# Modulator_V1p2.net
KiCad netlist of a schematic drawn in EAGLE
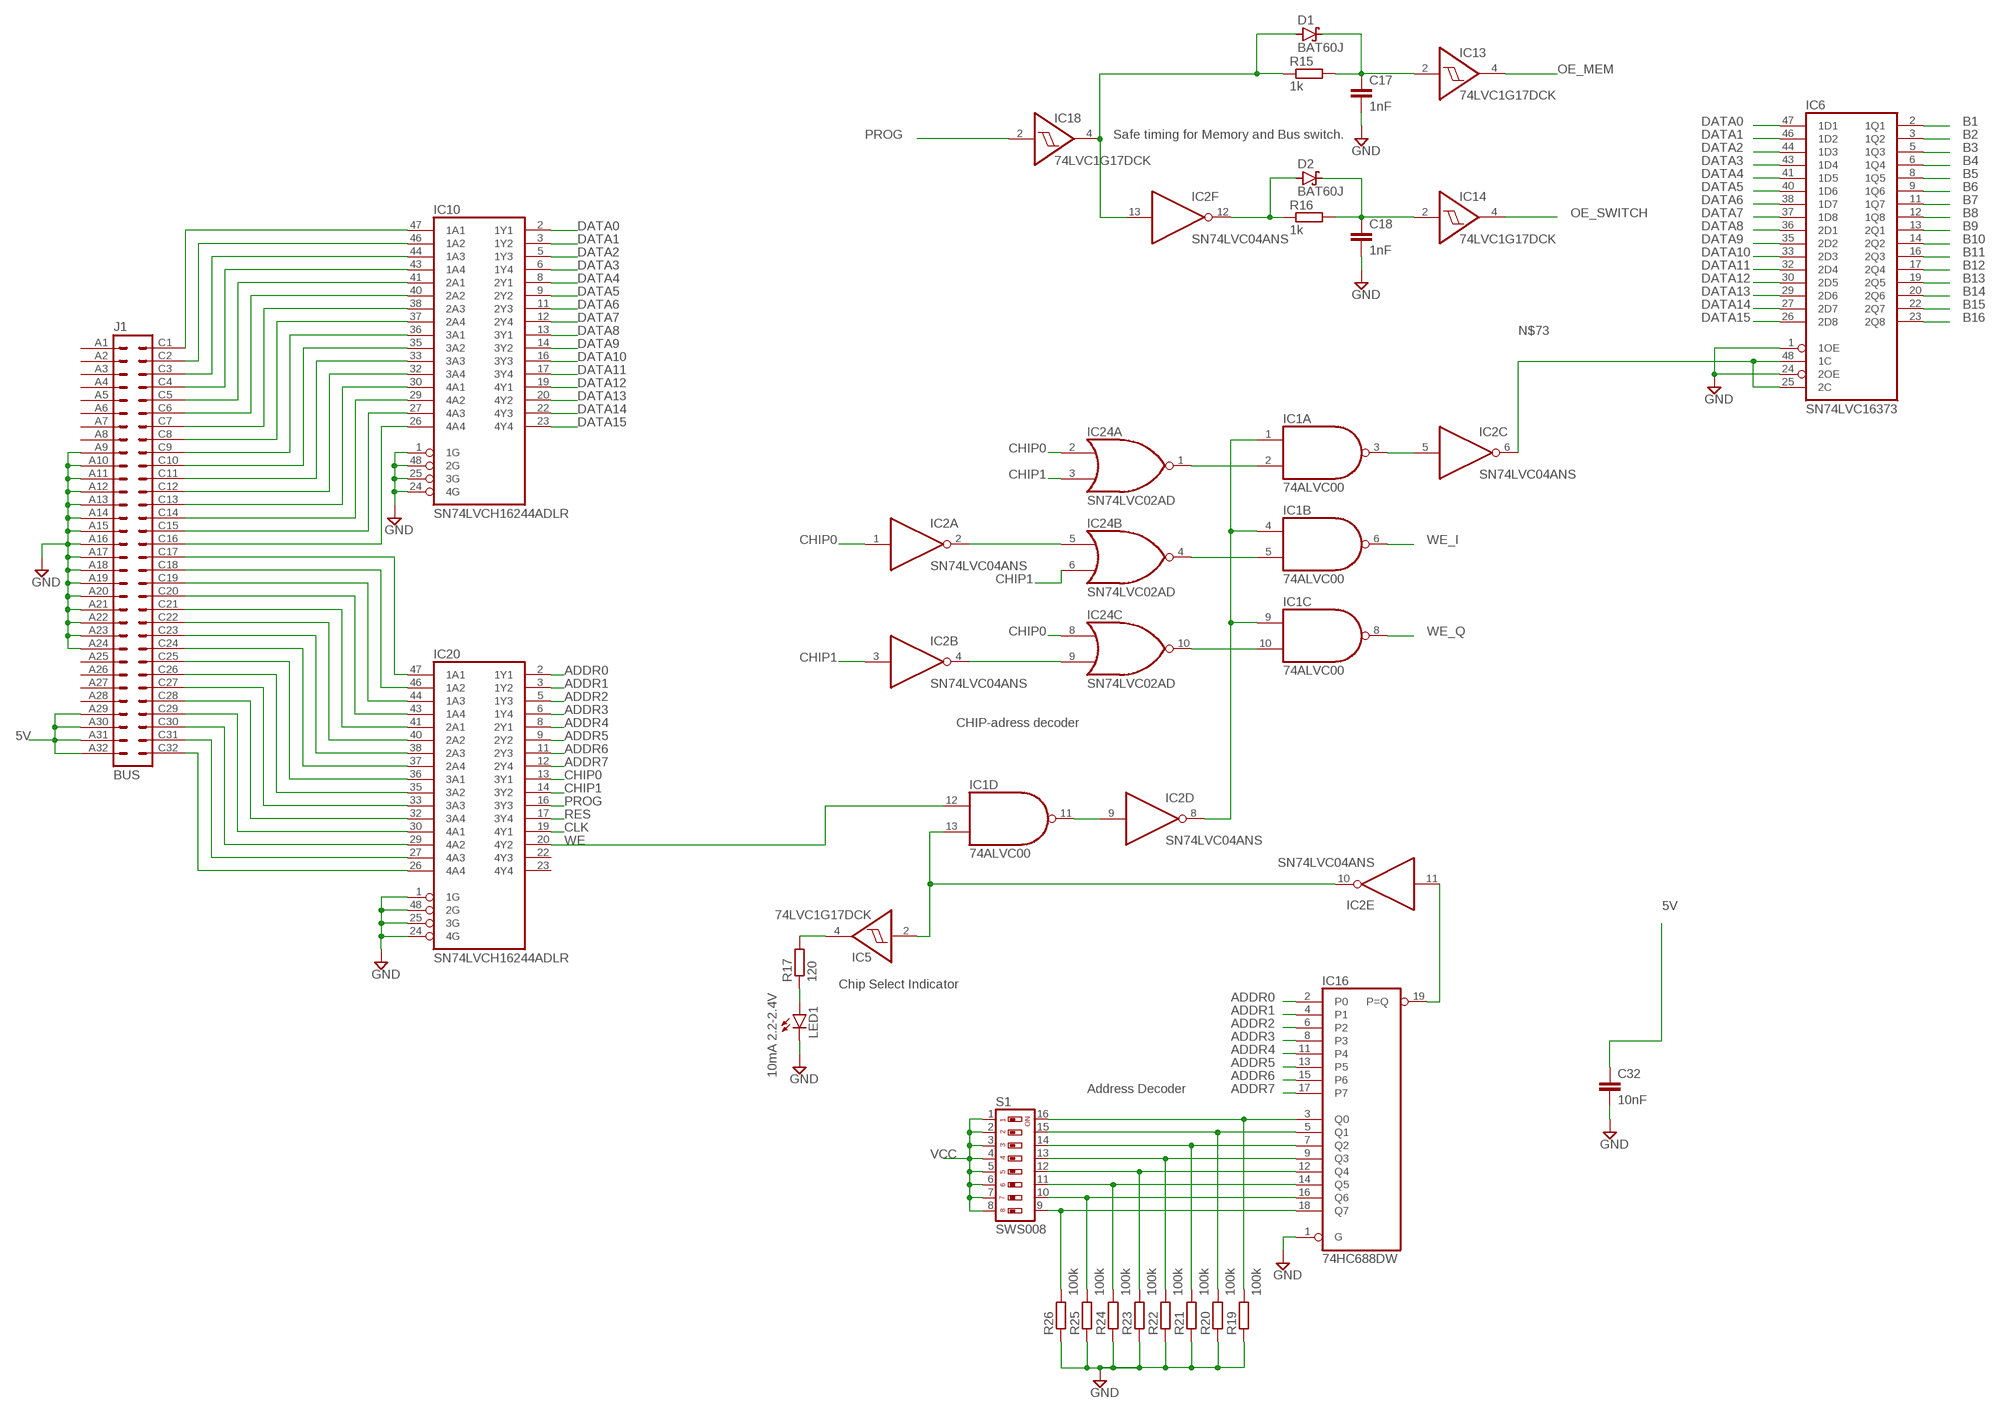
[diagram p0: schematic, sheet 1]
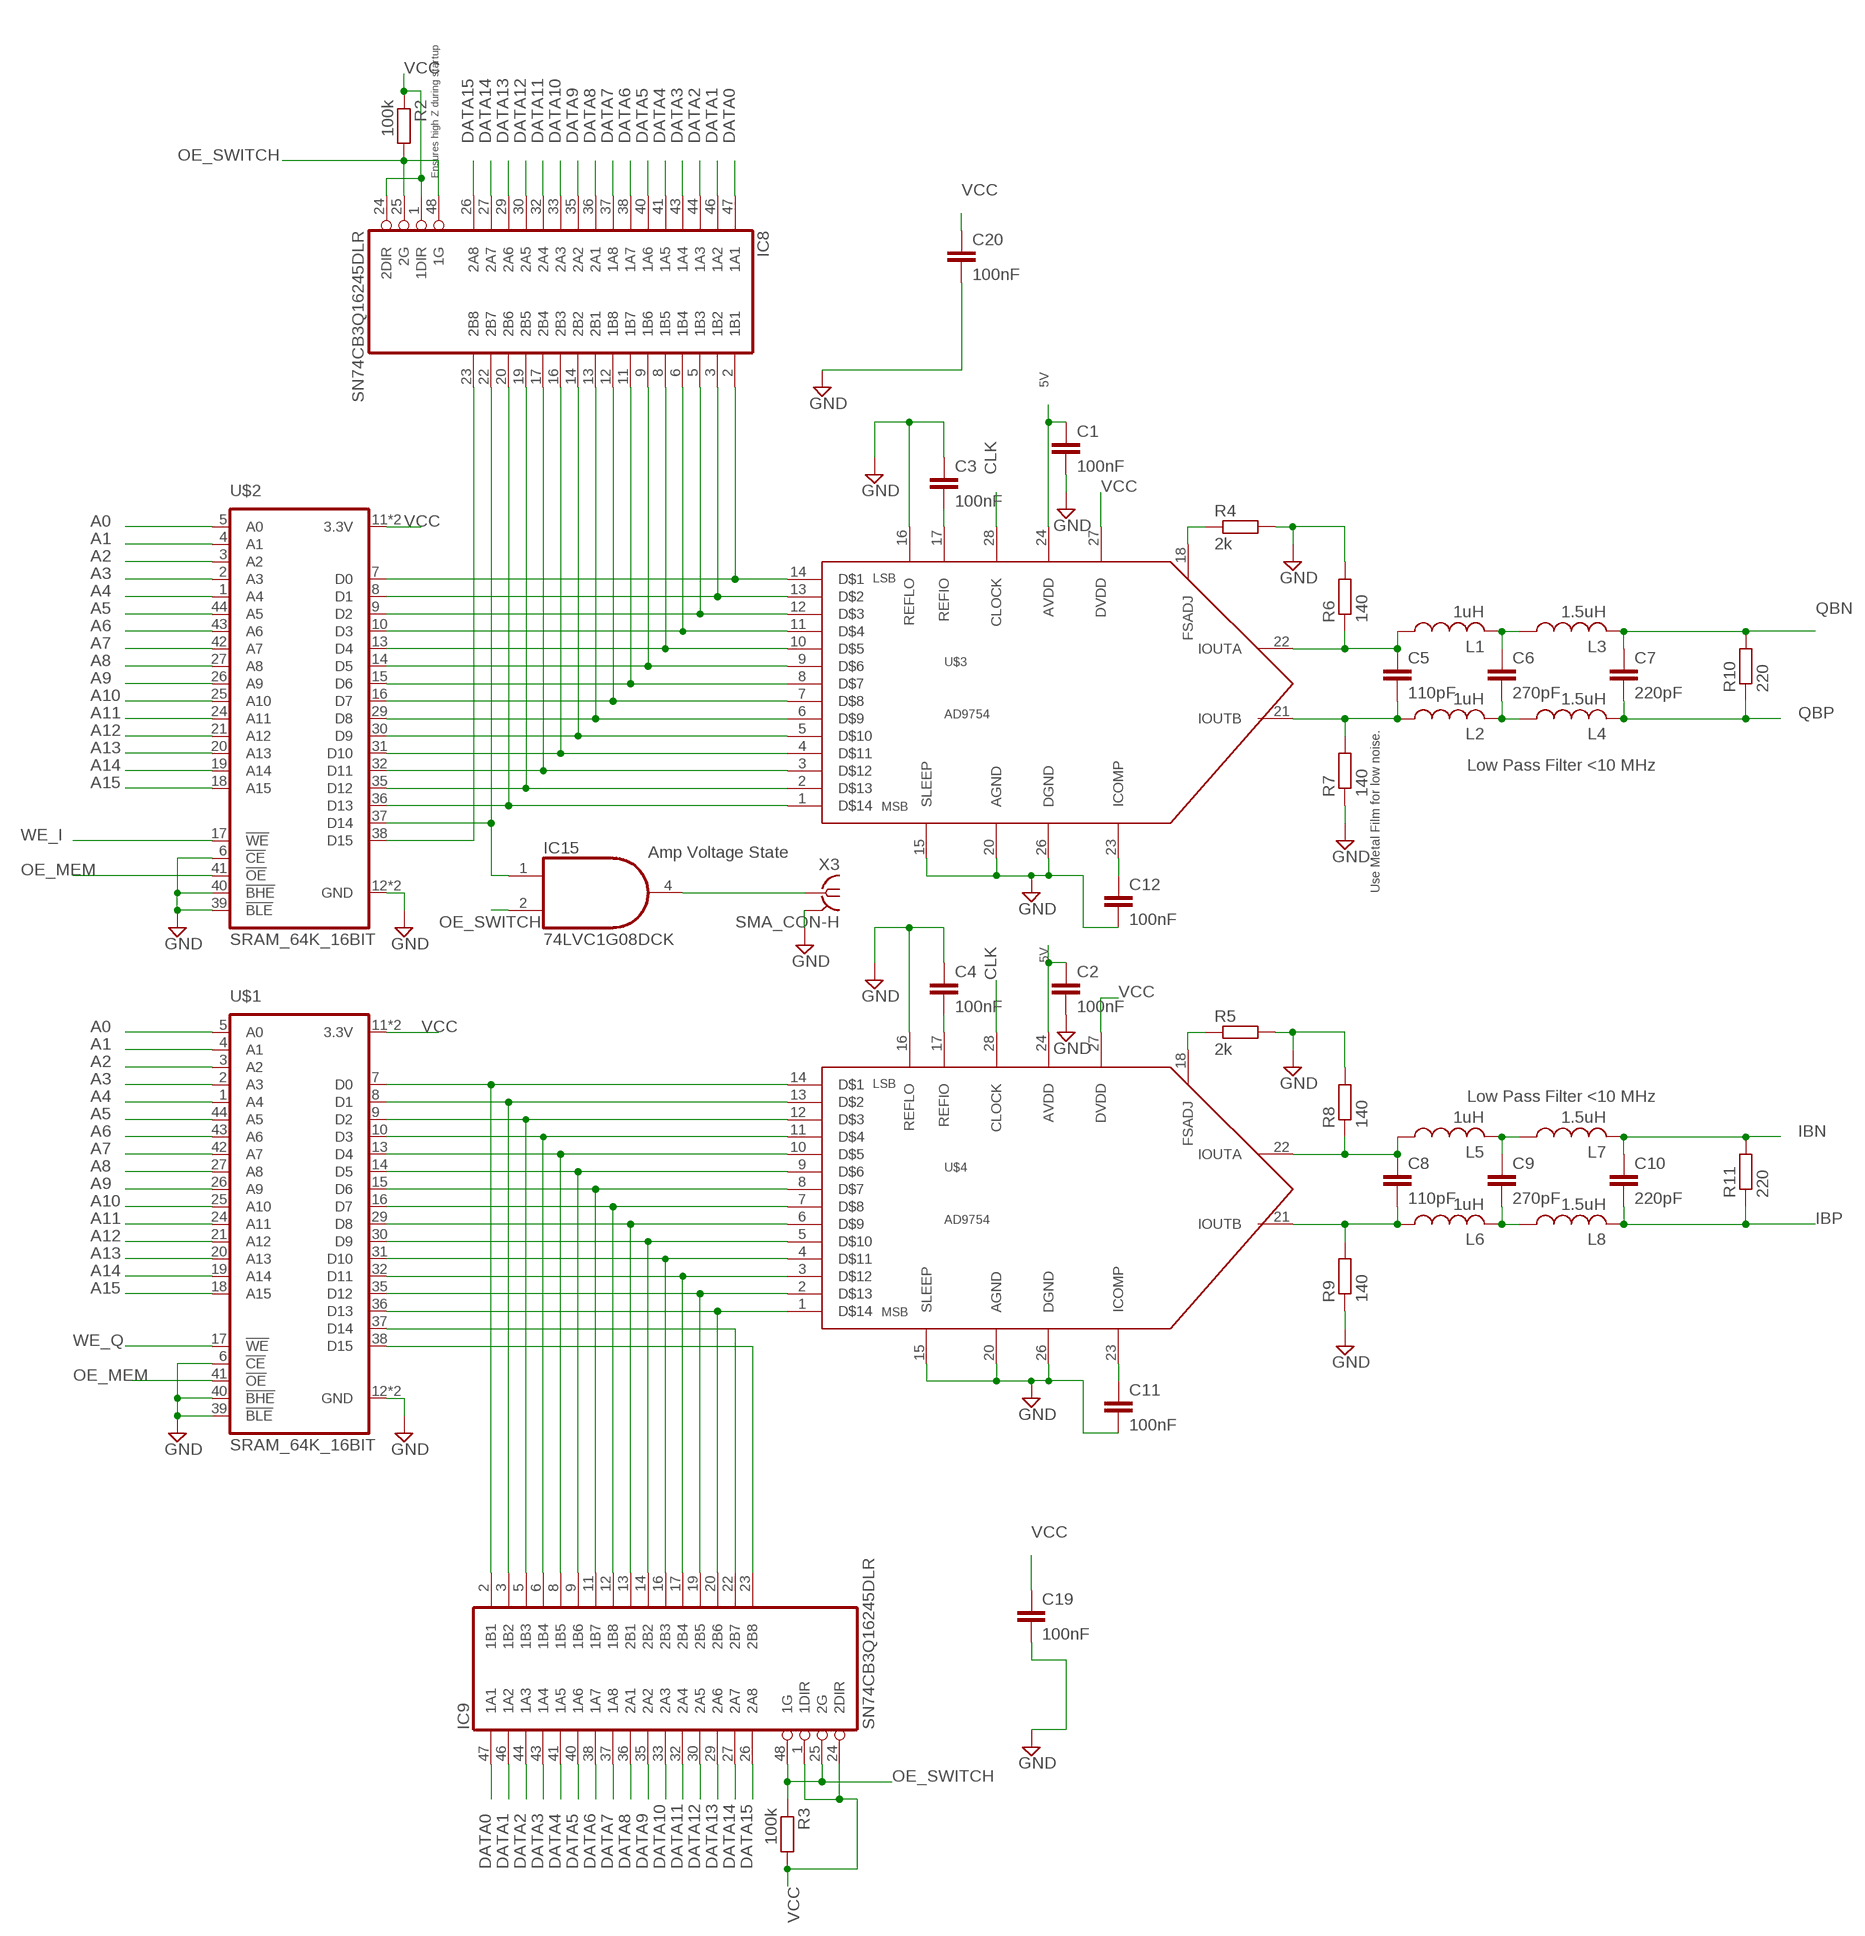
[diagram p1: schematic, sheet 2]
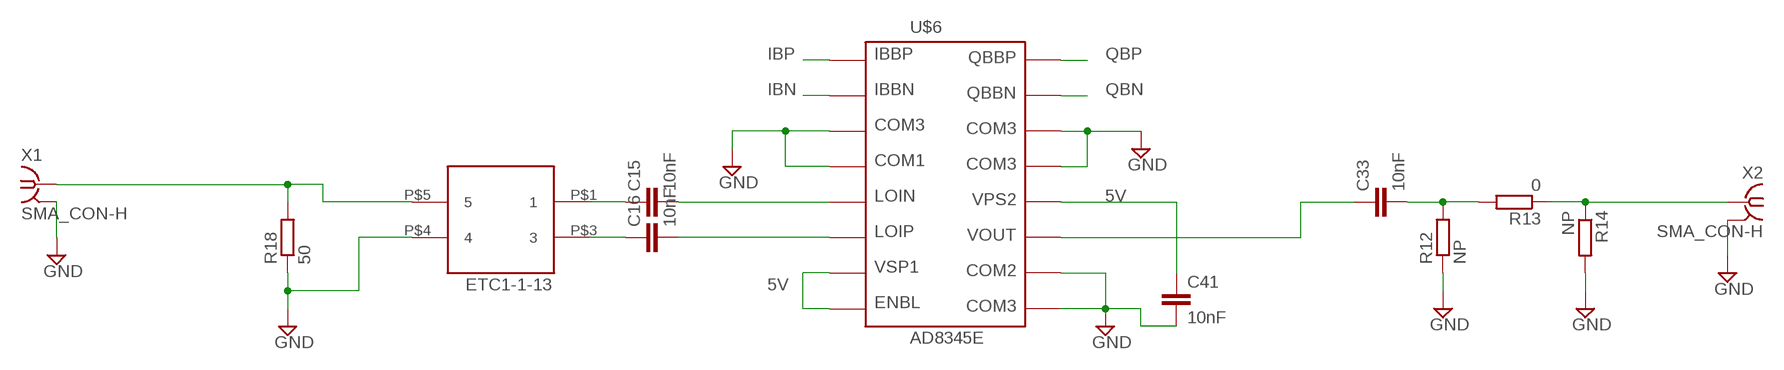
[diagram p2: schematic, sheet 3]
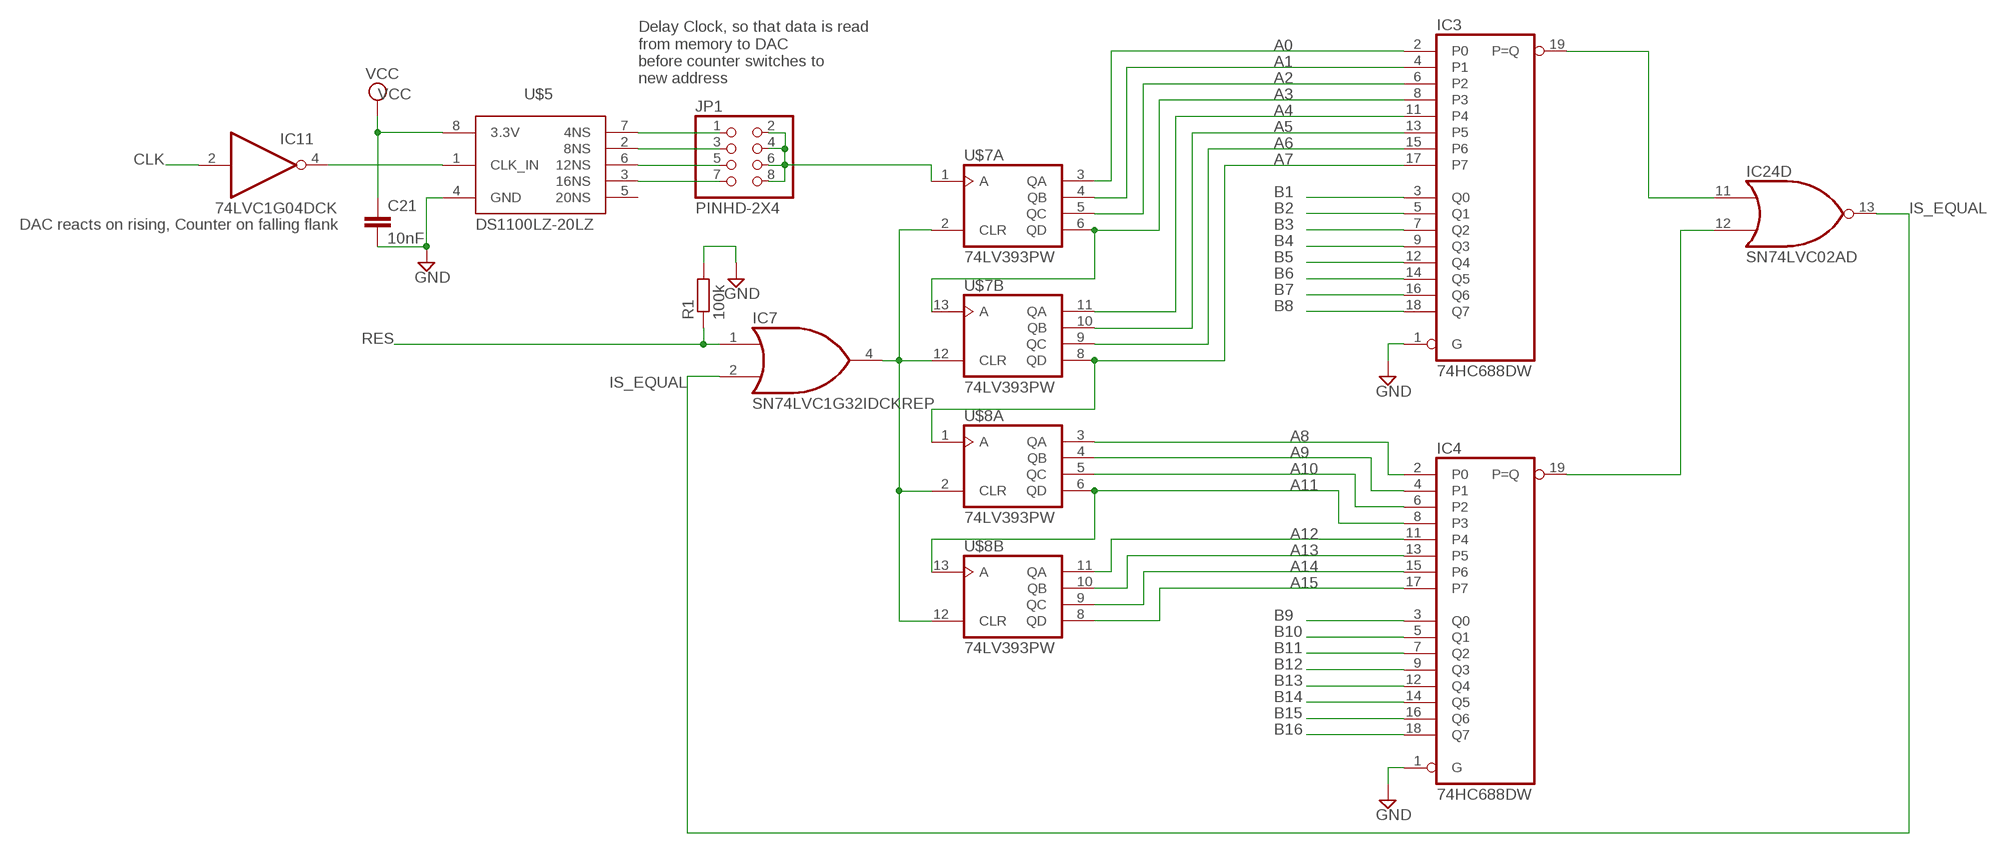
[diagram p3: schematic, sheet 4]
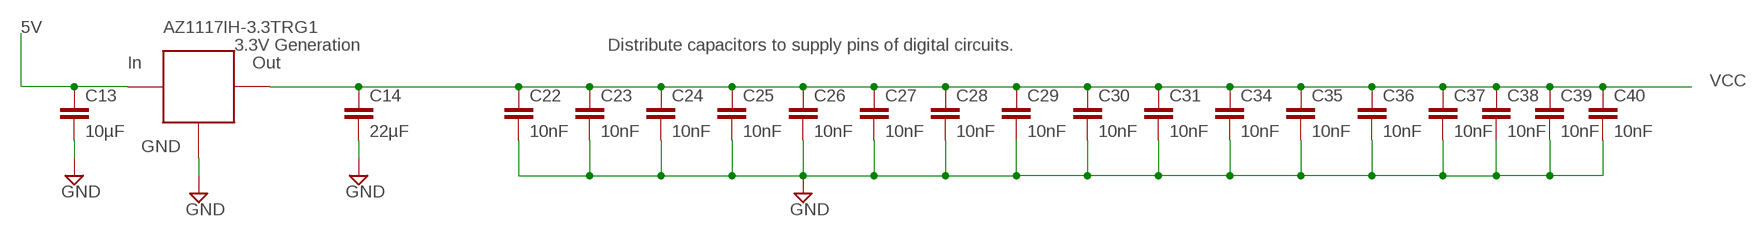
[diagram p4: schematic, sheet 5]

(export (version "E")
  (design (tool "Eeschema 10.0.6"))
  (components
    (comp (ref "C17")
      (value "1nF")
      (footprint "eagle-import:C0805")
      (libsource (lib "eagle-import") (part "C-EUC0805"))
    )
    (comp (ref "C18")
      (value "1nF")
      (footprint "eagle-import:C0805")
      (libsource (lib "eagle-import") (part "C-EUC0805"))
    )
    (comp (ref "C32")
      (value "10nF")
      (footprint "eagle-import:C0603")
      (libsource (lib "eagle-import") (part "C-EUC0603"))
    )
    (comp (ref "D1")
      (value "BAT60J")
      (footprint "eagle-import:SOD323_ST")
      (libsource (lib "eagle-import") (part "BAT60J"))
    )
    (comp (ref "D2")
      (value "BAT60J")
      (footprint "eagle-import:SOD323_ST")
      (libsource (lib "eagle-import") (part "BAT60J"))
    )
    (comp (ref "IC1")
      (value "74ALVC00")
      (footprint "eagle-import:SO14")
      (libsource (lib "eagle-import") (part "7400DALS"))
    )
    (comp (ref "IC2")
      (value "SN74LVC04ANS")
      (footprint "eagle-import:SO14")
      (libsource (lib "eagle-import") (part "7404DALS"))
    )
    (comp (ref "IC5")
      (value "74LVC1G17DCK")
      (footprint "eagle-import:SC70-5")
      (libsource (lib "eagle-import") (part "741G17DCKLVC"))
    )
    (comp (ref "IC6")
      (value "SN74LVC16373")
      (footprint "eagle-import:SSOP48DL")
      (libsource (lib "eagle-import") (part "74AC16373"))
    )
    (comp (ref "IC10")
      (value "SN74LVCH16244ADLR")
      (footprint "eagle-import:SSOP48DL")
      (libsource (lib "eagle-import") (part "74AC16244"))
    )
    (comp (ref "IC13")
      (value "74LVC1G17DCK")
      (footprint "eagle-import:SC70-5")
      (libsource (lib "eagle-import") (part "741G17DCKLVC"))
    )
    (comp (ref "IC14")
      (value "74LVC1G17DCK")
      (footprint "eagle-import:SC70-5")
      (libsource (lib "eagle-import") (part "741G17DCKLVC"))
    )
    (comp (ref "IC16")
      (value "74HC688DW")
      (footprint "eagle-import:SO20W")
      (libsource (lib "eagle-import") (part "74688DWHC"))
    )
    (comp (ref "IC18")
      (value "74LVC1G17DCK")
      (footprint "eagle-import:SC70-5")
      (libsource (lib "eagle-import") (part "741G17DCKLVC"))
    )
    (comp (ref "IC20")
      (value "SN74LVCH16244ADLR")
      (footprint "eagle-import:SSOP48DL")
      (libsource (lib "eagle-import") (part "74AC16244"))
    )
    (comp (ref "IC24")
      (value "SN74LVC02AD")
      (footprint "eagle-import:SO14")
      (libsource (lib "eagle-import") (part "7402DAS"))
    )
    (comp (ref "J1")
      (value "BUS")
      (footprint "eagle-import:VG64B")
      (libsource (lib "eagle-import") (part "VG64B"))
    )
    (comp (ref "LED1")
      (value "10mA 2.2-2.4V")
      (footprint "eagle-import:LED3MM")
      (libsource (lib "eagle-import") (part "LED3MM"))
    )
    (comp (ref "R15")
      (value "1k")
      (footprint "eagle-import:R0603")
      (libsource (lib "eagle-import") (part "R-EU_R0603"))
    )
    (comp (ref "R16")
      (value "1k")
      (footprint "eagle-import:R0603")
      (libsource (lib "eagle-import") (part "R-EU_R0603"))
    )
    (comp (ref "R17")
      (value "120")
      (footprint "eagle-import:R0603")
      (libsource (lib "eagle-import") (part "R-EU_R0603"))
    )
    (comp (ref "R19")
      (value "100k")
      (footprint "eagle-import:R0603")
      (libsource (lib "eagle-import") (part "R-EU_R0603"))
    )
    (comp (ref "R20")
      (value "100k")
      (footprint "eagle-import:R0603")
      (libsource (lib "eagle-import") (part "R-EU_R0603"))
    )
    (comp (ref "R21")
      (value "100k")
      (footprint "eagle-import:R0603")
      (libsource (lib "eagle-import") (part "R-EU_R0603"))
    )
    (comp (ref "R22")
      (value "100k")
      (footprint "eagle-import:R0603")
      (libsource (lib "eagle-import") (part "R-EU_R0603"))
    )
    (comp (ref "R23")
      (value "100k")
      (footprint "eagle-import:R0603")
      (libsource (lib "eagle-import") (part "R-EU_R0603"))
    )
    (comp (ref "R24")
      (value "100k")
      (footprint "eagle-import:R0603")
      (libsource (lib "eagle-import") (part "R-EU_R0603"))
    )
    (comp (ref "R25")
      (value "100k")
      (footprint "eagle-import:R0603")
      (libsource (lib "eagle-import") (part "R-EU_R0603"))
    )
    (comp (ref "R26")
      (value "100k")
      (footprint "eagle-import:R0603")
      (libsource (lib "eagle-import") (part "R-EU_R0603"))
    )
    (comp (ref "S1")
      (value "SWS008")
      (footprint "eagle-import:SMS-008")
      (libsource (lib "eagle-import") (part "SWS008"))
    )
    (comp (ref "C15")
      (value "10nF")
      (footprint "eagle-import:C0402")
      (libsource (lib "eagle-import") (part "C-EUC0402"))
    )
    (comp (ref "C16")
      (value "10nF")
      (footprint "eagle-import:C0402")
      (libsource (lib "eagle-import") (part "C-EUC0402"))
    )
    (comp (ref "C33")
      (value "10nF")
      (footprint "eagle-import:C0402")
      (libsource (lib "eagle-import") (part "C-EUC0402"))
    )
    (comp (ref "C41")
      (value "10nF")
      (footprint "eagle-import:C0603")
      (libsource (lib "eagle-import") (part "C-EUC0603"))
    )
    (comp (ref "R12")
      (value "NP")
      (footprint "eagle-import:R0805")
      (libsource (lib "eagle-import") (part "R-EU_R0805"))
    )
    (comp (ref "R13")
      (value "0")
      (footprint "eagle-import:R0805")
      (libsource (lib "eagle-import") (part "R-EU_R0805"))
    )
    (comp (ref "R14")
      (value "NP")
      (footprint "eagle-import:R0805")
      (libsource (lib "eagle-import") (part "R-EU_R0805"))
    )
    (comp (ref "R18")
      (value "50")
      (footprint "eagle-import:R0603")
      (libsource (lib "eagle-import") (part "R-EU_R0603"))
    )
    (comp (ref "U$6")
      (value "AD8345E")
      (footprint "eagle-import:TSSOP16EXP")
      (libsource (lib "eagle-import") (part "AD8345E"))
    )
    (comp (ref "U$12")
      (value "ETC1-1-13")
      (footprint "eagle-import:ETC1-1-13")
      (libsource (lib "eagle-import") (part "ETC1-1-13"))
    )
    (comp (ref "X1")
      (value "SMA_CON-H")
      (footprint "eagle-import:BU-SMA-H")
      (libsource (lib "eagle-import") (part "SMA_CON-H"))
    )
    (comp (ref "X2")
      (value "SMA_CON-H")
      (footprint "eagle-import:BU-SMA-H")
      (libsource (lib "eagle-import") (part "SMA_CON-H"))
    )
    (comp (ref "C1")
      (value "100nF")
      (footprint "eagle-import:C0603")
      (libsource (lib "eagle-import") (part "C-EUC0603"))
    )
    (comp (ref "C2")
      (value "100nF")
      (footprint "eagle-import:C0603")
      (libsource (lib "eagle-import") (part "C-EUC0603"))
    )
    (comp (ref "C3")
      (value "100nF")
      (footprint "eagle-import:C0603")
      (libsource (lib "eagle-import") (part "C-EUC0603"))
    )
    (comp (ref "C4")
      (value "100nF")
      (footprint "eagle-import:C0603")
      (libsource (lib "eagle-import") (part "C-EUC0603"))
    )
    (comp (ref "C5")
      (value "110pF")
      (footprint "eagle-import:C0603")
      (libsource (lib "eagle-import") (part "C-EUC0603"))
    )
    (comp (ref "C6")
      (value "270pF")
      (footprint "eagle-import:C0603")
      (libsource (lib "eagle-import") (part "C-EUC0603"))
    )
    (comp (ref "C7")
      (value "220pF")
      (footprint "eagle-import:C0603")
      (libsource (lib "eagle-import") (part "C-EUC0603"))
    )
    (comp (ref "C8")
      (value "110pF")
      (footprint "eagle-import:C0603")
      (libsource (lib "eagle-import") (part "C-EUC0603"))
    )
    (comp (ref "C9")
      (value "270pF")
      (footprint "eagle-import:C0603")
      (libsource (lib "eagle-import") (part "C-EUC0603"))
    )
    (comp (ref "C10")
      (value "220pF")
      (footprint "eagle-import:C0603")
      (libsource (lib "eagle-import") (part "C-EUC0603"))
    )
    (comp (ref "C11")
      (value "100nF")
      (footprint "eagle-import:C0603")
      (libsource (lib "eagle-import") (part "C-EUC0603"))
    )
    (comp (ref "C12")
      (value "100nF")
      (footprint "eagle-import:C0603")
      (libsource (lib "eagle-import") (part "C-EUC0603"))
    )
    (comp (ref "C19")
      (value "100nF")
      (footprint "eagle-import:C0603")
      (libsource (lib "eagle-import") (part "C-EUC0603"))
    )
    (comp (ref "C20")
      (value "100nF")
      (footprint "eagle-import:C0603")
      (libsource (lib "eagle-import") (part "C-EUC0603"))
    )
    (comp (ref "IC8")
      (value "SN74CB3Q16245DLR")
      (footprint "eagle-import:SSOP48DL")
      (libsource (lib "eagle-import") (part "74AC16245"))
    )
    (comp (ref "IC9")
      (value "SN74CB3Q16245DLR")
      (footprint "eagle-import:SSOP48DL")
      (libsource (lib "eagle-import") (part "74AC16245"))
    )
    (comp (ref "IC15")
      (value "74LVC1G08DCK")
      (footprint "eagle-import:SC70-5")
      (libsource (lib "eagle-import") (part "741G08DCKLVC"))
    )
    (comp (ref "L1")
      (value "1uH")
      (footprint "eagle-import:L2012C")
      (libsource (lib "eagle-import") (part "L-USL2012C"))
    )
    (comp (ref "L2")
      (value "1uH")
      (footprint "eagle-import:L2012C")
      (libsource (lib "eagle-import") (part "L-USL2012C"))
    )
    (comp (ref "L3")
      (value "1.5uH")
      (footprint "eagle-import:L2012C")
      (libsource (lib "eagle-import") (part "L-USL2012C"))
    )
    (comp (ref "L4")
      (value "1.5uH")
      (footprint "eagle-import:L2012C")
      (libsource (lib "eagle-import") (part "L-USL2012C"))
    )
    (comp (ref "L5")
      (value "1uH")
      (footprint "eagle-import:L2012C")
      (libsource (lib "eagle-import") (part "L-USL2012C"))
    )
    (comp (ref "L6")
      (value "1uH")
      (footprint "eagle-import:L2012C")
      (libsource (lib "eagle-import") (part "L-USL2012C"))
    )
    (comp (ref "L7")
      (value "1.5uH")
      (footprint "eagle-import:L2012C")
      (libsource (lib "eagle-import") (part "L-USL2012C"))
    )
    (comp (ref "L8")
      (value "1.5uH")
      (footprint "eagle-import:L2012C")
      (libsource (lib "eagle-import") (part "L-USL2012C"))
    )
    (comp (ref "R2")
      (value "100k")
      (footprint "eagle-import:R0603")
      (libsource (lib "eagle-import") (part "R-EU_R0603"))
    )
    (comp (ref "R3")
      (value "100k")
      (footprint "eagle-import:R0603")
      (libsource (lib "eagle-import") (part "R-EU_R0603"))
    )
    (comp (ref "R4")
      (value "2k")
      (footprint "eagle-import:R0603")
      (libsource (lib "eagle-import") (part "R-EU_R0603"))
    )
    (comp (ref "R5")
      (value "2k")
      (footprint "eagle-import:R0603")
      (libsource (lib "eagle-import") (part "R-EU_R0603"))
    )
    (comp (ref "R6")
      (value "140")
      (footprint "eagle-import:R0603")
      (libsource (lib "eagle-import") (part "R-EU_R0603"))
    )
    (comp (ref "R7")
      (value "140")
      (footprint "eagle-import:R0603")
      (libsource (lib "eagle-import") (part "R-EU_R0603"))
    )
    (comp (ref "R8")
      (value "140")
      (footprint "eagle-import:R0603")
      (libsource (lib "eagle-import") (part "R-EU_R0603"))
    )
    (comp (ref "R9")
      (value "140")
      (footprint "eagle-import:R0603")
      (libsource (lib "eagle-import") (part "R-EU_R0603"))
    )
    (comp (ref "R10")
      (value "220")
      (footprint "eagle-import:R0603")
      (libsource (lib "eagle-import") (part "R-EU_R0603"))
    )
    (comp (ref "R11")
      (value "220")
      (footprint "eagle-import:R0603")
      (libsource (lib "eagle-import") (part "R-EU_R0603"))
    )
    (comp (ref "U$1")
      (value "SRAM_64K_16BIT")
      (footprint "eagle-import:TSOPII-Z44")
      (libsource (lib "eagle-import") (part "SRAM_64K_16BIT"))
    )
    (comp (ref "U$2")
      (value "SRAM_64K_16BIT")
      (footprint "eagle-import:TSOPII-Z44")
      (libsource (lib "eagle-import") (part "SRAM_64K_16BIT"))
    )
    (comp (ref "U$3")
      (value "AD9754")
      (footprint "eagle-import:TSSOP28")
      (libsource (lib "eagle-import") (part "AD9754"))
    )
    (comp (ref "U$4")
      (value "AD9754")
      (footprint "eagle-import:TSSOP28")
      (libsource (lib "eagle-import") (part "AD9754"))
    )
    (comp (ref "X3")
      (value "SMA_CON-H")
      (footprint "eagle-import:BU-SMA-H")
      (libsource (lib "eagle-import") (part "SMA_CON-H"))
    )
    (comp (ref "C21")
      (value "10nF")
      (footprint "eagle-import:C0603")
      (libsource (lib "eagle-import") (part "C-EUC0603"))
    )
    (comp (ref "IC3")
      (value "74HC688DW")
      (footprint "eagle-import:SO20W")
      (libsource (lib "eagle-import") (part "74688DWHC"))
    )
    (comp (ref "IC4")
      (value "74HC688DW")
      (footprint "eagle-import:SO20W")
      (libsource (lib "eagle-import") (part "74688DWHC"))
    )
    (comp (ref "IC7")
      (value "SN74LVC1G32IDCKREP")
      (footprint "eagle-import:SC70-5")
      (libsource (lib "eagle-import") (part "741G32DCKAHC"))
    )
    (comp (ref "IC11")
      (value "74LVC1G04DCK")
      (footprint "eagle-import:SC70-5")
      (libsource (lib "eagle-import") (part "741G04DCKLVC"))
    )
    (comp (ref "JP1")
      (value "PINHD-2X4")
      (footprint "eagle-import:2X04")
      (libsource (lib "eagle-import") (part "PINHD-2X4"))
    )
    (comp (ref "R1")
      (value "100k")
      (footprint "eagle-import:R0603")
      (libsource (lib "eagle-import") (part "R-EU_R0603"))
    )
    (comp (ref "U$5")
      (value "DS1100LZ-20LZ")
      (footprint "eagle-import:SO-08")
      (libsource (lib "eagle-import") (part "DS1100LZ-20LZ"))
    )
    (comp (ref "U$7")
      (value "74LV393PW")
      (footprint "eagle-import:TSSOP14")
      (libsource (lib "eagle-import") (part "74LV393PW"))
    )
    (comp (ref "U$8")
      (value "74LV393PW")
      (footprint "eagle-import:TSSOP14")
      (libsource (lib "eagle-import") (part "74LV393PW"))
    )
    (comp (ref "C13")
      (value "10µF")
      (footprint "eagle-import:C1206")
      (libsource (lib "eagle-import") (part "C-EUC1206"))
    )
    (comp (ref "C14")
      (value "22µF")
      (footprint "eagle-import:C1206")
      (libsource (lib "eagle-import") (part "C-EUC1206"))
    )
    (comp (ref "C22")
      (value "10nF")
      (footprint "eagle-import:C0603")
      (libsource (lib "eagle-import") (part "C-EUC0603"))
    )
    (comp (ref "C23")
      (value "10nF")
      (footprint "eagle-import:C0603")
      (libsource (lib "eagle-import") (part "C-EUC0603"))
    )
    (comp (ref "C24")
      (value "10nF")
      (footprint "eagle-import:C0603")
      (libsource (lib "eagle-import") (part "C-EUC0603"))
    )
    (comp (ref "C25")
      (value "10nF")
      (footprint "eagle-import:C0603")
      (libsource (lib "eagle-import") (part "C-EUC0603"))
    )
    (comp (ref "C26")
      (value "10nF")
      (footprint "eagle-import:C0603")
      (libsource (lib "eagle-import") (part "C-EUC0603"))
    )
    (comp (ref "C27")
      (value "10nF")
      (footprint "eagle-import:C0603")
      (libsource (lib "eagle-import") (part "C-EUC0603"))
    )
    (comp (ref "C28")
      (value "10nF")
      (footprint "eagle-import:C0603")
      (libsource (lib "eagle-import") (part "C-EUC0603"))
    )
    (comp (ref "C29")
      (value "10nF")
      (footprint "eagle-import:C0603")
      (libsource (lib "eagle-import") (part "C-EUC0603"))
    )
    (comp (ref "C30")
      (value "10nF")
      (footprint "eagle-import:C0603")
      (libsource (lib "eagle-import") (part "C-EUC0603"))
    )
    (comp (ref "C31")
      (value "10nF")
      (footprint "eagle-import:C0603")
      (libsource (lib "eagle-import") (part "C-EUC0603"))
    )
    (comp (ref "C34")
      (value "10nF")
      (footprint "eagle-import:C0603")
      (libsource (lib "eagle-import") (part "C-EUC0603"))
    )
    (comp (ref "C35")
      (value "10nF")
      (footprint "eagle-import:C0603")
      (libsource (lib "eagle-import") (part "C-EUC0603"))
    )
    (comp (ref "C36")
      (value "10nF")
      (footprint "eagle-import:C0603")
      (libsource (lib "eagle-import") (part "C-EUC0603"))
    )
    (comp (ref "C37")
      (value "10nF")
      (footprint "eagle-import:C0603")
      (libsource (lib "eagle-import") (part "C-EUC0603"))
    )
    (comp (ref "C38")
      (value "10nF")
      (footprint "eagle-import:C0603")
      (libsource (lib "eagle-import") (part "C-EUC0603"))
    )
    (comp (ref "C39")
      (value "10nF")
      (footprint "eagle-import:C0603")
      (libsource (lib "eagle-import") (part "C-EUC0603"))
    )
    (comp (ref "C40")
      (value "10nF")
      (footprint "eagle-import:C0603")
      (libsource (lib "eagle-import") (part "C-EUC0603"))
    )
    (comp (ref "U$9")
      (value "AZ1117IH-3.3TRG1")
      (footprint "eagle-import:SOT223")
      (libsource (lib "eagle-import") (part "LT1117"))
    )
  )
  (nets
    (net (code "1") (name "5V") (class "Default")
      (node (ref "C1") (pin "1") (pinfunction "1_1") (pintype "passive"))
      (node (ref "C13") (pin "1") (pinfunction "1_1") (pintype "passive"))
      (node (ref "C2") (pin "1") (pinfunction "1_1") (pintype "passive"))
      (node (ref "C32") (pin "1") (pinfunction "1_1") (pintype "passive"))
      (node (ref "C41") (pin "1") (pinfunction "1_1") (pintype "passive"))
      (node (ref "J1") (pin "A29") (pinfunction "A29_A29") (pintype "passive"))
      (node (ref "J1") (pin "A30") (pinfunction "A30_A30") (pintype "passive"))
      (node (ref "J1") (pin "A31") (pinfunction "A31_A31") (pintype "passive"))
      (node (ref "J1") (pin "A32") (pinfunction "A32_A32") (pintype "passive"))
      (node (ref "U$3") (pin "24") (pinfunction "AVDD_24") (pintype "bidirectional"))
      (node (ref "U$4") (pin "24") (pinfunction "AVDD_24") (pintype "bidirectional"))
      (node (ref "U$6") (pin "12") (pinfunction "P$12_12") (pintype "bidirectional"))
      (node (ref "U$6") (pin "7") (pinfunction "P$7_7") (pintype "bidirectional"))
      (node (ref "U$6") (pin "8") (pinfunction "P$8_8") (pintype "bidirectional"))
      (node (ref "U$9") (pin "3") (pinfunction "IN_3") (pintype "bidirectional"))
    )
    (net (code "2") (name "A0") (class "Default")
      (node (ref "IC3") (pin "2") (pinfunction "P0_2") (pintype "input"))
      (node (ref "U$1") (pin "5") (pinfunction "A0_5") (pintype "input"))
      (node (ref "U$2") (pin "5") (pinfunction "A0_5") (pintype "input"))
      (node (ref "U$7") (pin "3") (pinfunction "QA_3") (pintype "output"))
    )
    (net (code "3") (name "A1") (class "Default")
      (node (ref "IC3") (pin "4") (pinfunction "P1_4") (pintype "input"))
      (node (ref "U$1") (pin "4") (pinfunction "A1_4") (pintype "input"))
      (node (ref "U$2") (pin "4") (pinfunction "A1_4") (pintype "input"))
      (node (ref "U$7") (pin "4") (pinfunction "QB_4") (pintype "output"))
    )
    (net (code "4") (name "A2") (class "Default")
      (node (ref "IC3") (pin "6") (pinfunction "P2_6") (pintype "input"))
      (node (ref "U$1") (pin "3") (pinfunction "A2_3") (pintype "input"))
      (node (ref "U$2") (pin "3") (pinfunction "A2_3") (pintype "input"))
      (node (ref "U$7") (pin "5") (pinfunction "QC_5") (pintype "output"))
    )
    (net (code "5") (name "A3") (class "Default")
      (node (ref "IC3") (pin "8") (pinfunction "P3_8") (pintype "input"))
      (node (ref "U$1") (pin "2") (pinfunction "A3_2") (pintype "input"))
      (node (ref "U$2") (pin "2") (pinfunction "A3_2") (pintype "input"))
      (node (ref "U$7") (pin "13") (pinfunction "A_13") (pintype "input"))
      (node (ref "U$7") (pin "6") (pinfunction "QD_6") (pintype "output"))
    )
    (net (code "6") (name "A4") (class "Default")
      (node (ref "IC3") (pin "11") (pinfunction "P4_11") (pintype "input"))
      (node (ref "U$1") (pin "1") (pinfunction "A4_1") (pintype "input"))
      (node (ref "U$2") (pin "1") (pinfunction "A4_1") (pintype "input"))
      (node (ref "U$7") (pin "11") (pinfunction "QA_11") (pintype "output"))
    )
    (net (code "7") (name "A5") (class "Default")
      (node (ref "IC3") (pin "13") (pinfunction "P5_13") (pintype "input"))
      (node (ref "U$1") (pin "44") (pinfunction "A5_44") (pintype "input"))
      (node (ref "U$2") (pin "44") (pinfunction "A5_44") (pintype "input"))
      (node (ref "U$7") (pin "10") (pinfunction "QB_10") (pintype "output"))
    )
    (net (code "8") (name "A6") (class "Default")
      (node (ref "IC3") (pin "15") (pinfunction "P6_15") (pintype "input"))
      (node (ref "U$1") (pin "43") (pinfunction "A6_43") (pintype "input"))
      (node (ref "U$2") (pin "43") (pinfunction "A6_43") (pintype "input"))
      (node (ref "U$7") (pin "9") (pinfunction "QC_9") (pintype "output"))
    )
    (net (code "9") (name "A7") (class "Default")
      (node (ref "IC3") (pin "17") (pinfunction "P7_17") (pintype "input"))
      (node (ref "U$1") (pin "42") (pinfunction "A7_42") (pintype "input"))
      (node (ref "U$2") (pin "42") (pinfunction "A7_42") (pintype "input"))
      (node (ref "U$7") (pin "8") (pinfunction "QD_8") (pintype "output"))
      (node (ref "U$8") (pin "1") (pinfunction "A_1") (pintype "input"))
    )
    (net (code "10") (name "A8") (class "Default")
      (node (ref "IC4") (pin "2") (pinfunction "P0_2") (pintype "input"))
      (node (ref "U$1") (pin "27") (pinfunction "A8_27") (pintype "input"))
      (node (ref "U$2") (pin "27") (pinfunction "A8_27") (pintype "input"))
      (node (ref "U$8") (pin "3") (pinfunction "QA_3") (pintype "output"))
    )
    (net (code "11") (name "A9") (class "Default")
      (node (ref "IC4") (pin "4") (pinfunction "P1_4") (pintype "input"))
      (node (ref "U$1") (pin "26") (pinfunction "A9_26") (pintype "input"))
      (node (ref "U$2") (pin "26") (pinfunction "A9_26") (pintype "input"))
      (node (ref "U$8") (pin "4") (pinfunction "QB_4") (pintype "output"))
    )
    (net (code "12") (name "A10") (class "Default")
      (node (ref "IC4") (pin "6") (pinfunction "P2_6") (pintype "input"))
      (node (ref "U$1") (pin "25") (pinfunction "A10_25") (pintype "input"))
      (node (ref "U$2") (pin "25") (pinfunction "A10_25") (pintype "input"))
      (node (ref "U$8") (pin "5") (pinfunction "QC_5") (pintype "output"))
    )
    (net (code "13") (name "A11") (class "Default")
      (node (ref "IC4") (pin "8") (pinfunction "P3_8") (pintype "input"))
      (node (ref "U$1") (pin "24") (pinfunction "A11_24") (pintype "input"))
      (node (ref "U$2") (pin "24") (pinfunction "A11_24") (pintype "input"))
      (node (ref "U$8") (pin "13") (pinfunction "A_13") (pintype "input"))
      (node (ref "U$8") (pin "6") (pinfunction "QD_6") (pintype "output"))
    )
    (net (code "14") (name "A12") (class "Default")
      (node (ref "IC4") (pin "11") (pinfunction "P4_11") (pintype "input"))
      (node (ref "U$1") (pin "21") (pinfunction "A12_21") (pintype "input"))
      (node (ref "U$2") (pin "21") (pinfunction "A12_21") (pintype "input"))
      (node (ref "U$8") (pin "11") (pinfunction "QA_11") (pintype "output"))
    )
    (net (code "15") (name "A13") (class "Default")
      (node (ref "IC4") (pin "13") (pinfunction "P5_13") (pintype "input"))
      (node (ref "U$1") (pin "20") (pinfunction "A13_20") (pintype "input"))
      (node (ref "U$2") (pin "20") (pinfunction "A13_20") (pintype "input"))
      (node (ref "U$8") (pin "10") (pinfunction "QB_10") (pintype "output"))
    )
    (net (code "16") (name "A14") (class "Default")
      (node (ref "IC4") (pin "15") (pinfunction "P6_15") (pintype "input"))
      (node (ref "U$1") (pin "19") (pinfunction "A14_19") (pintype "input"))
      (node (ref "U$2") (pin "19") (pinfunction "A14_19") (pintype "input"))
      (node (ref "U$8") (pin "9") (pinfunction "QC_9") (pintype "output"))
    )
    (net (code "17") (name "A15") (class "Default")
      (node (ref "IC4") (pin "17") (pinfunction "P7_17") (pintype "input"))
      (node (ref "U$1") (pin "18") (pinfunction "A15_18") (pintype "input"))
      (node (ref "U$2") (pin "18") (pinfunction "A15_18") (pintype "input"))
      (node (ref "U$8") (pin "8") (pinfunction "QD_8") (pintype "output"))
    )
    (net (code "18") (name "ADDR0") (class "Default")
      (node (ref "IC16") (pin "2") (pinfunction "P0_2") (pintype "input"))
      (node (ref "IC20") (pin "2") (pinfunction "1Y1_2") (pintype "tri_state"))
    )
    (net (code "19") (name "ADDR1") (class "Default")
      (node (ref "IC16") (pin "4") (pinfunction "P1_4") (pintype "input"))
      (node (ref "IC20") (pin "3") (pinfunction "1Y2_3") (pintype "tri_state"))
    )
    (net (code "20") (name "ADDR2") (class "Default")
      (node (ref "IC16") (pin "6") (pinfunction "P2_6") (pintype "input"))
      (node (ref "IC20") (pin "5") (pinfunction "1Y3_5") (pintype "tri_state"))
    )
    (net (code "21") (name "ADDR3") (class "Default")
      (node (ref "IC16") (pin "8") (pinfunction "P3_8") (pintype "input"))
      (node (ref "IC20") (pin "6") (pinfunction "1Y4_6") (pintype "tri_state"))
    )
    (net (code "22") (name "ADDR4") (class "Default")
      (node (ref "IC16") (pin "11") (pinfunction "P4_11") (pintype "input"))
      (node (ref "IC20") (pin "8") (pinfunction "2Y1_8") (pintype "tri_state"))
    )
    (net (code "23") (name "ADDR5") (class "Default")
      (node (ref "IC16") (pin "13") (pinfunction "P5_13") (pintype "input"))
      (node (ref "IC20") (pin "9") (pinfunction "2Y2_9") (pintype "tri_state"))
    )
    (net (code "24") (name "ADDR6") (class "Default")
      (node (ref "IC16") (pin "15") (pinfunction "P6_15") (pintype "input"))
      (node (ref "IC20") (pin "11") (pinfunction "2Y3_11") (pintype "tri_state"))
    )
    (net (code "25") (name "ADDR7") (class "Default")
      (node (ref "IC16") (pin "17") (pinfunction "P7_17") (pintype "input"))
      (node (ref "IC20") (pin "12") (pinfunction "2Y4_12") (pintype "tri_state"))
    )
    (net (code "26") (name "B1") (class "Default")
      (node (ref "IC3") (pin "3") (pinfunction "Q0_3") (pintype "input"))
      (node (ref "IC6") (pin "2") (pinfunction "1Q1_2") (pintype "tri_state"))
    )
    (net (code "27") (name "B2") (class "Default")
      (node (ref "IC3") (pin "5") (pinfunction "Q1_5") (pintype "input"))
      (node (ref "IC6") (pin "3") (pinfunction "1Q2_3") (pintype "tri_state"))
    )
    (net (code "28") (name "B3") (class "Default")
      (node (ref "IC3") (pin "7") (pinfunction "Q2_7") (pintype "input"))
      (node (ref "IC6") (pin "5") (pinfunction "1Q3_5") (pintype "tri_state"))
    )
    (net (code "29") (name "B4") (class "Default")
      (node (ref "IC3") (pin "9") (pinfunction "Q3_9") (pintype "input"))
      (node (ref "IC6") (pin "6") (pinfunction "1Q4_6") (pintype "tri_state"))
    )
    (net (code "30") (name "B5") (class "Default")
      (node (ref "IC3") (pin "12") (pinfunction "Q4_12") (pintype "input"))
      (node (ref "IC6") (pin "8") (pinfunction "1Q5_8") (pintype "tri_state"))
    )
    (net (code "31") (name "B6") (class "Default")
      (node (ref "IC3") (pin "14") (pinfunction "Q5_14") (pintype "input"))
      (node (ref "IC6") (pin "9") (pinfunction "1Q6_9") (pintype "tri_state"))
    )
    (net (code "32") (name "B7") (class "Default")
      (node (ref "IC3") (pin "16") (pinfunction "Q6_16") (pintype "input"))
      (node (ref "IC6") (pin "11") (pinfunction "1Q7_11") (pintype "tri_state"))
    )
    (net (code "33") (name "B8") (class "Default")
      (node (ref "IC3") (pin "18") (pinfunction "Q7_18") (pintype "input"))
      (node (ref "IC6") (pin "12") (pinfunction "1Q8_12") (pintype "tri_state"))
    )
    (net (code "34") (name "B9") (class "Default")
      (node (ref "IC4") (pin "3") (pinfunction "Q0_3") (pintype "input"))
      (node (ref "IC6") (pin "13") (pinfunction "2Q1_13") (pintype "tri_state"))
    )
    (net (code "35") (name "B10") (class "Default")
      (node (ref "IC4") (pin "5") (pinfunction "Q1_5") (pintype "input"))
      (node (ref "IC6") (pin "14") (pinfunction "2Q2_14") (pintype "tri_state"))
    )
    (net (code "36") (name "B11") (class "Default")
      (node (ref "IC4") (pin "7") (pinfunction "Q2_7") (pintype "input"))
      (node (ref "IC6") (pin "16") (pinfunction "2Q3_16") (pintype "tri_state"))
    )
    (net (code "37") (name "B12") (class "Default")
      (node (ref "IC4") (pin "9") (pinfunction "Q3_9") (pintype "input"))
      (node (ref "IC6") (pin "17") (pinfunction "2Q4_17") (pintype "tri_state"))
    )
    (net (code "38") (name "B13") (class "Default")
      (node (ref "IC4") (pin "12") (pinfunction "Q4_12") (pintype "input"))
      (node (ref "IC6") (pin "19") (pinfunction "2Q5_19") (pintype "tri_state"))
    )
    (net (code "39") (name "B14") (class "Default")
      (node (ref "IC4") (pin "14") (pinfunction "Q5_14") (pintype "input"))
      (node (ref "IC6") (pin "20") (pinfunction "2Q6_20") (pintype "tri_state"))
    )
    (net (code "40") (name "B15") (class "Default")
      (node (ref "IC4") (pin "16") (pinfunction "Q6_16") (pintype "input"))
      (node (ref "IC6") (pin "22") (pinfunction "2Q7_22") (pintype "tri_state"))
    )
    (net (code "41") (name "B16") (class "Default")
      (node (ref "IC4") (pin "18") (pinfunction "Q7_18") (pintype "input"))
      (node (ref "IC6") (pin "23") (pinfunction "2Q8_23") (pintype "tri_state"))
    )
    (net (code "42") (name "CHIP0") (class "Default")
      (node (ref "IC2") (pin "1") (pinfunction "I_1") (pintype "input"))
      (node (ref "IC20") (pin "13") (pinfunction "3Y1_13") (pintype "tri_state"))
      (node (ref "IC24") (pin "2") (pinfunction "I0_2") (pintype "input"))
      (node (ref "IC24") (pin "8") (pinfunction "I0_8") (pintype "input"))
    )
    (net (code "43") (name "CHIP1") (class "Default")
      (node (ref "IC2") (pin "3") (pinfunction "I_3") (pintype "input"))
      (node (ref "IC20") (pin "14") (pinfunction "3Y2_14") (pintype "tri_state"))
      (node (ref "IC24") (pin "3") (pinfunction "I1_3") (pintype "input"))
      (node (ref "IC24") (pin "6") (pinfunction "I1_6") (pintype "input"))
    )
    (net (code "44") (name "CLK") (class "Default")
      (node (ref "IC11") (pin "2") (pinfunction "I_2") (pintype "input"))
      (node (ref "IC20") (pin "19") (pinfunction "4Y1_19") (pintype "tri_state"))
      (node (ref "U$3") (pin "28") (pinfunction "CLOCK_28") (pintype "bidirectional"))
      (node (ref "U$4") (pin "28") (pinfunction "CLOCK_28") (pintype "bidirectional"))
    )
    (net (code "45") (name "DATA0") (class "Default")
      (node (ref "IC10") (pin "2") (pinfunction "1Y1_2") (pintype "tri_state"))
      (node (ref "IC6") (pin "47") (pinfunction "1D1_47") (pintype "input"))
      (node (ref "IC8") (pin "47") (pinfunction "1A1_47") (pintype "bidirectional"))
      (node (ref "IC9") (pin "47") (pinfunction "1A1_47") (pintype "bidirectional"))
    )
    (net (code "46") (name "DATA1") (class "Default")
      (node (ref "IC10") (pin "3") (pinfunction "1Y2_3") (pintype "tri_state"))
      (node (ref "IC6") (pin "46") (pinfunction "1D2_46") (pintype "input"))
      (node (ref "IC8") (pin "46") (pinfunction "1A2_46") (pintype "bidirectional"))
      (node (ref "IC9") (pin "46") (pinfunction "1A2_46") (pintype "bidirectional"))
    )
    (net (code "47") (name "DATA2") (class "Default")
      (node (ref "IC10") (pin "5") (pinfunction "1Y3_5") (pintype "tri_state"))
      (node (ref "IC6") (pin "44") (pinfunction "1D3_44") (pintype "input"))
      (node (ref "IC8") (pin "44") (pinfunction "1A3_44") (pintype "bidirectional"))
      (node (ref "IC9") (pin "44") (pinfunction "1A3_44") (pintype "bidirectional"))
    )
    (net (code "48") (name "DATA3") (class "Default")
      (node (ref "IC10") (pin "6") (pinfunction "1Y4_6") (pintype "tri_state"))
      (node (ref "IC6") (pin "43") (pinfunction "1D4_43") (pintype "input"))
      (node (ref "IC8") (pin "43") (pinfunction "1A4_43") (pintype "bidirectional"))
      (node (ref "IC9") (pin "43") (pinfunction "1A4_43") (pintype "bidirectional"))
    )
    (net (code "49") (name "DATA4") (class "Default")
      (node (ref "IC10") (pin "8") (pinfunction "2Y1_8") (pintype "tri_state"))
      (node (ref "IC6") (pin "41") (pinfunction "1D5_41") (pintype "input"))
      (node (ref "IC8") (pin "41") (pinfunction "1A5_41") (pintype "bidirectional"))
      (node (ref "IC9") (pin "41") (pinfunction "1A5_41") (pintype "bidirectional"))
    )
    (net (code "50") (name "DATA5") (class "Default")
      (node (ref "IC10") (pin "9") (pinfunction "2Y2_9") (pintype "tri_state"))
      (node (ref "IC6") (pin "40") (pinfunction "1D6_40") (pintype "input"))
      (node (ref "IC8") (pin "40") (pinfunction "1A6_40") (pintype "bidirectional"))
      (node (ref "IC9") (pin "40") (pinfunction "1A6_40") (pintype "bidirectional"))
    )
    (net (code "51") (name "DATA6") (class "Default")
      (node (ref "IC10") (pin "11") (pinfunction "2Y3_11") (pintype "tri_state"))
      (node (ref "IC6") (pin "38") (pinfunction "1D7_38") (pintype "input"))
      (node (ref "IC8") (pin "38") (pinfunction "1A7_38") (pintype "bidirectional"))
      (node (ref "IC9") (pin "38") (pinfunction "1A7_38") (pintype "bidirectional"))
    )
    (net (code "52") (name "DATA7") (class "Default")
      (node (ref "IC10") (pin "12") (pinfunction "2Y4_12") (pintype "tri_state"))
      (node (ref "IC6") (pin "37") (pinfunction "1D8_37") (pintype "input"))
      (node (ref "IC8") (pin "37") (pinfunction "1A8_37") (pintype "bidirectional"))
      (node (ref "IC9") (pin "37") (pinfunction "1A8_37") (pintype "bidirectional"))
    )
    (net (code "53") (name "DATA8") (class "Default")
      (node (ref "IC10") (pin "13") (pinfunction "3Y1_13") (pintype "tri_state"))
      (node (ref "IC6") (pin "36") (pinfunction "2D1_36") (pintype "input"))
      (node (ref "IC8") (pin "36") (pinfunction "2A1_36") (pintype "bidirectional"))
      (node (ref "IC9") (pin "36") (pinfunction "2A1_36") (pintype "bidirectional"))
    )
    (net (code "54") (name "DATA9") (class "Default")
      (node (ref "IC10") (pin "14") (pinfunction "3Y2_14") (pintype "tri_state"))
      (node (ref "IC6") (pin "35") (pinfunction "2D2_35") (pintype "input"))
      (node (ref "IC8") (pin "35") (pinfunction "2A2_35") (pintype "bidirectional"))
      (node (ref "IC9") (pin "35") (pinfunction "2A2_35") (pintype "bidirectional"))
    )
    (net (code "55") (name "DATA10") (class "Default")
      (node (ref "IC10") (pin "16") (pinfunction "3Y3_16") (pintype "tri_state"))
      (node (ref "IC6") (pin "33") (pinfunction "2D3_33") (pintype "input"))
      (node (ref "IC8") (pin "33") (pinfunction "2A3_33") (pintype "bidirectional"))
      (node (ref "IC9") (pin "33") (pinfunction "2A3_33") (pintype "bidirectional"))
    )
    (net (code "56") (name "DATA11") (class "Default")
      (node (ref "IC10") (pin "17") (pinfunction "3Y4_17") (pintype "tri_state"))
      (node (ref "IC6") (pin "32") (pinfunction "2D4_32") (pintype "input"))
      (node (ref "IC8") (pin "32") (pinfunction "2A4_32") (pintype "bidirectional"))
      (node (ref "IC9") (pin "32") (pinfunction "2A4_32") (pintype "bidirectional"))
    )
    (net (code "57") (name "DATA12") (class "Default")
      (node (ref "IC10") (pin "19") (pinfunction "4Y1_19") (pintype "tri_state"))
      (node (ref "IC6") (pin "30") (pinfunction "2D5_30") (pintype "input"))
      (node (ref "IC8") (pin "30") (pinfunction "2A5_30") (pintype "bidirectional"))
      (node (ref "IC9") (pin "30") (pinfunction "2A5_30") (pintype "bidirectional"))
    )
    (net (code "58") (name "DATA13") (class "Default")
      (node (ref "IC10") (pin "20") (pinfunction "4Y2_20") (pintype "tri_state"))
      (node (ref "IC6") (pin "29") (pinfunction "2D6_29") (pintype "input"))
      (node (ref "IC8") (pin "29") (pinfunction "2A6_29") (pintype "bidirectional"))
      (node (ref "IC9") (pin "29") (pinfunction "2A6_29") (pintype "bidirectional"))
    )
    (net (code "59") (name "DATA14") (class "Default")
      (node (ref "IC10") (pin "22") (pinfunction "4Y3_22") (pintype "tri_state"))
      (node (ref "IC6") (pin "27") (pinfunction "2D7_27") (pintype "input"))
      (node (ref "IC8") (pin "27") (pinfunction "2A7_27") (pintype "bidirectional"))
      (node (ref "IC9") (pin "27") (pinfunction "2A7_27") (pintype "bidirectional"))
    )
    (net (code "60") (name "DATA15") (class "Default")
      (node (ref "IC10") (pin "23") (pinfunction "4Y4_23") (pintype "tri_state"))
      (node (ref "IC6") (pin "26") (pinfunction "2D8_26") (pintype "input"))
      (node (ref "IC8") (pin "26") (pinfunction "2A8_26") (pintype "bidirectional"))
      (node (ref "IC9") (pin "26") (pinfunction "2A8_26") (pintype "bidirectional"))
    )
    (net (code "61") (name "GND") (class "Default")
      (node (ref "C1") (pin "2") (pinfunction "2_2") (pintype "passive"))
      (node (ref "C11") (pin "2") (pinfunction "2_2") (pintype "passive"))
      (node (ref "C12") (pin "2") (pinfunction "2_2") (pintype "passive"))
      (node (ref "C13") (pin "2") (pinfunction "2_2") (pintype "passive"))
      (node (ref "C14") (pin "2") (pinfunction "2_2") (pintype "passive"))
      (node (ref "C17") (pin "2") (pinfunction "2_2") (pintype "passive"))
      (node (ref "C18") (pin "2") (pinfunction "2_2") (pintype "passive"))
      (node (ref "C19") (pin "2") (pinfunction "2_2") (pintype "passive"))
      (node (ref "C2") (pin "2") (pinfunction "2_2") (pintype "passive"))
      (node (ref "C20") (pin "2") (pinfunction "2_2") (pintype "passive"))
      (node (ref "C21") (pin "2") (pinfunction "2_2") (pintype "passive"))
      (node (ref "C22") (pin "2") (pinfunction "2_2") (pintype "passive"))
      (node (ref "C23") (pin "2") (pinfunction "2_2") (pintype "passive"))
      (node (ref "C24") (pin "2") (pinfunction "2_2") (pintype "passive"))
      (node (ref "C25") (pin "2") (pinfunction "2_2") (pintype "passive"))
      (node (ref "C26") (pin "2") (pinfunction "2_2") (pintype "passive"))
      (node (ref "C27") (pin "2") (pinfunction "2_2") (pintype "passive"))
      (node (ref "C28") (pin "2") (pinfunction "2_2") (pintype "passive"))
      (node (ref "C29") (pin "2") (pinfunction "2_2") (pintype "passive"))
      (node (ref "C3") (pin "1") (pinfunction "1_1") (pintype "passive"))
      (node (ref "C30") (pin "2") (pinfunction "2_2") (pintype "passive"))
      (node (ref "C31") (pin "2") (pinfunction "2_2") (pintype "passive"))
      (node (ref "C32") (pin "2") (pinfunction "2_2") (pintype "passive"))
      (node (ref "C34") (pin "2") (pinfunction "2_2") (pintype "passive"))
      (node (ref "C35") (pin "2") (pinfunction "2_2") (pintype "passive"))
      (node (ref "C36") (pin "2") (pinfunction "2_2") (pintype "passive"))
      (node (ref "C37") (pin "2") (pinfunction "2_2") (pintype "passive"))
      (node (ref "C38") (pin "2") (pinfunction "2_2") (pintype "passive"))
      (node (ref "C39") (pin "2") (pinfunction "2_2") (pintype "passive"))
      (node (ref "C4") (pin "1") (pinfunction "1_1") (pintype "passive"))
      (node (ref "C40") (pin "2") (pinfunction "2_2") (pintype "passive"))
      (node (ref "C41") (pin "2") (pinfunction "2_2") (pintype "passive"))
      (node (ref "IC10") (pin "1") (pinfunction "1G_1") (pintype "input"))
      (node (ref "IC10") (pin "24") (pinfunction "4G_24") (pintype "input"))
      (node (ref "IC10") (pin "25") (pinfunction "3G_25") (pintype "input"))
      (node (ref "IC10") (pin "48") (pinfunction "2G_48") (pintype "input"))
      (node (ref "IC16") (pin "1") (pinfunction "G_1") (pintype "input"))
      (node (ref "IC20") (pin "1") (pinfunction "1G_1") (pintype "input"))
      (node (ref "IC20") (pin "24") (pinfunction "4G_24") (pintype "input"))
      (node (ref "IC20") (pin "25") (pinfunction "3G_25") (pintype "input"))
      (node (ref "IC20") (pin "48") (pinfunction "2G_48") (pintype "input"))
      (node (ref "IC3") (pin "1") (pinfunction "G_1") (pintype "input"))
      (node (ref "IC4") (pin "1") (pinfunction "G_1") (pintype "input"))
      (node (ref "IC6") (pin "1") (pinfunction "1OE_1") (pintype "input"))
      (node (ref "IC6") (pin "24") (pinfunction "2OE_24") (pintype "input"))
      (node (ref "J1") (pin "A10") (pinfunction "A10_A10") (pintype "passive"))
      (node (ref "J1") (pin "A11") (pinfunction "A11_A11") (pintype "passive"))
      (node (ref "J1") (pin "A12") (pinfunction "A12_A12") (pintype "passive"))
      (node (ref "J1") (pin "A13") (pinfunction "A13_A13") (pintype "passive"))
      (node (ref "J1") (pin "A14") (pinfunction "A14_A14") (pintype "passive"))
      (node (ref "J1") (pin "A15") (pinfunction "A15_A15") (pintype "passive"))
      (node (ref "J1") (pin "A16") (pinfunction "A16_A16") (pintype "passive"))
      (node (ref "J1") (pin "A17") (pinfunction "A17_A17") (pintype "passive"))
      (node (ref "J1") (pin "A18") (pinfunction "A18_A18") (pintype "passive"))
      (node (ref "J1") (pin "A19") (pinfunction "A19_A19") (pintype "passive"))
      (node (ref "J1") (pin "A20") (pinfunction "A20_A20") (pintype "passive"))
      (node (ref "J1") (pin "A21") (pinfunction "A21_A21") (pintype "passive"))
      (node (ref "J1") (pin "A22") (pinfunction "A22_A22") (pintype "passive"))
      (node (ref "J1") (pin "A23") (pinfunction "A23_A23") (pintype "passive"))
      (node (ref "J1") (pin "A24") (pinfunction "A24_A24") (pintype "passive"))
      (node (ref "J1") (pin "A9") (pinfunction "A9_A9") (pintype "passive"))
      (node (ref "LED1") (pin "K") (pinfunction "C_K") (pintype "passive"))
      (node (ref "R1") (pin "2") (pinfunction "2_2") (pintype "passive"))
      (node (ref "R12") (pin "1") (pinfunction "1_1") (pintype "passive"))
      (node (ref "R14") (pin "2") (pinfunction "2_2") (pintype "passive"))
      (node (ref "R18") (pin "1") (pinfunction "1_1") (pintype "passive"))
      (node (ref "R19") (pin "1") (pinfunction "1_1") (pintype "passive"))
      (node (ref "R20") (pin "1") (pinfunction "1_1") (pintype "passive"))
      (node (ref "R21") (pin "1") (pinfunction "1_1") (pintype "passive"))
      (node (ref "R22") (pin "1") (pinfunction "1_1") (pintype "passive"))
      (node (ref "R23") (pin "1") (pinfunction "1_1") (pintype "passive"))
      (node (ref "R24") (pin "1") (pinfunction "1_1") (pintype "passive"))
      (node (ref "R25") (pin "1") (pinfunction "1_1") (pintype "passive"))
      (node (ref "R26") (pin "1") (pinfunction "1_1") (pintype "passive"))
      (node (ref "R4") (pin "2") (pinfunction "2_2") (pintype "passive"))
      (node (ref "R5") (pin "2") (pinfunction "2_2") (pintype "passive"))
      (node (ref "R6") (pin "2") (pinfunction "2_2") (pintype "passive"))
      (node (ref "R7") (pin "1") (pinfunction "1_1") (pintype "passive"))
      (node (ref "R8") (pin "2") (pinfunction "2_2") (pintype "passive"))
      (node (ref "R9") (pin "1") (pinfunction "1_1") (pintype "passive"))
      (node (ref "U$1") (pin "12") (pinfunction "GND_12") (pintype "bidirectional"))
      (node (ref "U$1") (pin "34") (pinfunction "GND_34") (pintype "bidirectional"))
      (node (ref "U$1") (pin "39") (pinfunction "~{BLE}_39") (pintype "input"))
      (node (ref "U$1") (pin "40") (pinfunction "~{BHE}_40") (pintype "input"))
      (node (ref "U$1") (pin "6") (pinfunction "~{CE}_6") (pintype "input"))
      (node (ref "U$12") (pin "P$4") (pinfunction "4_P$4") (pintype "bidirectional"))
      (node (ref "U$2") (pin "12") (pinfunction "GND_12") (pintype "bidirectional"))
      (node (ref "U$2") (pin "34") (pinfunction "GND_34") (pintype "bidirectional"))
      (node (ref "U$2") (pin "39") (pinfunction "~{BLE}_39") (pintype "input"))
      (node (ref "U$2") (pin "40") (pinfunction "~{BHE}_40") (pintype "input"))
      (node (ref "U$2") (pin "6") (pinfunction "~{CE}_6") (pintype "input"))
      (node (ref "U$3") (pin "15") (pinfunction "SLEEP_15") (pintype "bidirectional"))
      (node (ref "U$3") (pin "16") (pinfunction "REFLO_16") (pintype "bidirectional"))
      (node (ref "U$3") (pin "20") (pinfunction "AGND_20") (pintype "bidirectional"))
      (node (ref "U$3") (pin "26") (pinfunction "DGND_26") (pintype "bidirectional"))
      (node (ref "U$4") (pin "15") (pinfunction "SLEEP_15") (pintype "bidirectional"))
      (node (ref "U$4") (pin "16") (pinfunction "REFLO_16") (pintype "bidirectional"))
      (node (ref "U$4") (pin "20") (pinfunction "AGND_20") (pintype "bidirectional"))
      (node (ref "U$4") (pin "26") (pinfunction "DGND_26") (pintype "bidirectional"))
      (node (ref "U$5") (pin "4") (pinfunction "GND_4") (pintype "bidirectional"))
      (node (ref "U$6") (pin "10") (pinfunction "P$10_10") (pintype "bidirectional"))
      (node (ref "U$6") (pin "13") (pinfunction "P$13_13") (pintype "bidirectional"))
      (node (ref "U$6") (pin "14") (pinfunction "P$14_14") (pintype "bidirectional"))
      (node (ref "U$6") (pin "3") (pinfunction "P$3_3") (pintype "bidirectional"))
      (node (ref "U$6") (pin "4") (pinfunction "P$4_4") (pintype "bidirectional"))
      (node (ref "U$6") (pin "9") (pinfunction "P$9_9") (pintype "bidirectional"))
      (node (ref "U$6") (pin "EXP") (pinfunction "P$9_EXP") (pintype "bidirectional"))
      (node (ref "U$9") (pin "1") (pinfunction "GND_1") (pintype "bidirectional"))
      (node (ref "X1") (pin "2") (pinfunction "GND_2") (pintype "passive"))
      (node (ref "X1") (pin "3") (pinfunction "GND_3") (pintype "passive"))
      (node (ref "X1") (pin "4") (pinfunction "GND_4") (pintype "passive"))
      (node (ref "X1") (pin "5") (pinfunction "GND_5") (pintype "passive"))
      (node (ref "X2") (pin "2") (pinfunction "GND_2") (pintype "passive"))
      (node (ref "X2") (pin "3") (pinfunction "GND_3") (pintype "passive"))
      (node (ref "X2") (pin "4") (pinfunction "GND_4") (pintype "passive"))
      (node (ref "X2") (pin "5") (pinfunction "GND_5") (pintype "passive"))
      (node (ref "X3") (pin "2") (pinfunction "GND_2") (pintype "passive"))
      (node (ref "X3") (pin "3") (pinfunction "GND_3") (pintype "passive"))
      (node (ref "X3") (pin "4") (pinfunction "GND_4") (pintype "passive"))
      (node (ref "X3") (pin "5") (pinfunction "GND_5") (pintype "passive"))
    )
    (net (code "62") (name "IBN") (class "Default")
      (node (ref "C10") (pin "1") (pinfunction "1_1") (pintype "passive"))
      (node (ref "L7") (pin "2") (pinfunction "2_2") (pintype "passive"))
      (node (ref "R11") (pin "2") (pinfunction "2_2") (pintype "passive"))
      (node (ref "U$6") (pin "2") (pinfunction "P$2_2") (pintype "bidirectional"))
    )
    (net (code "63") (name "IBP") (class "Default")
      (node (ref "C10") (pin "2") (pinfunction "2_2") (pintype "passive"))
      (node (ref "L8") (pin "2") (pinfunction "2_2") (pintype "passive"))
      (node (ref "R11") (pin "1") (pinfunction "1_1") (pintype "passive"))
      (node (ref "U$6") (pin "1") (pinfunction "P$1_1") (pintype "bidirectional"))
    )
    (net (code "64") (name "IS_EQUAL") (class "Default")
      (node (ref "IC24") (pin "13") (pinfunction "O_13") (pintype "output"))
      (node (ref "IC7") (pin "2") (pinfunction "I1_2") (pintype "input"))
    )
    (net (code "65") (name "N$73") (class "Default")
      (node (ref "IC2") (pin "6") (pinfunction "O_6") (pintype "output"))
      (node (ref "IC6") (pin "25") (pinfunction "2C_25") (pintype "input"))
      (node (ref "IC6") (pin "48") (pinfunction "1C_48") (pintype "input"))
    )
    (net (code "66") (name "Net-(C6-Pad1)") (class "Default")
      (node (ref "C6") (pin "1") (pinfunction "1_1") (pintype "passive"))
      (node (ref "L1") (pin "2") (pinfunction "2_2") (pintype "passive"))
      (node (ref "L3") (pin "1") (pinfunction "1_1") (pintype "passive"))
    )
    (net (code "67") (name "Net-(C6-Pad2)") (class "Default")
      (node (ref "C6") (pin "2") (pinfunction "2_2") (pintype "passive"))
      (node (ref "L2") (pin "2") (pinfunction "2_2") (pintype "passive"))
      (node (ref "L4") (pin "1") (pinfunction "1_1") (pintype "passive"))
    )
    (net (code "68") (name "Net-(C9-Pad1)") (class "Default")
      (node (ref "C9") (pin "1") (pinfunction "1_1") (pintype "passive"))
      (node (ref "L5") (pin "2") (pinfunction "2_2") (pintype "passive"))
      (node (ref "L7") (pin "1") (pinfunction "1_1") (pintype "passive"))
    )
    (net (code "69") (name "Net-(C9-Pad2)") (class "Default")
      (node (ref "C9") (pin "2") (pinfunction "2_2") (pintype "passive"))
      (node (ref "L6") (pin "2") (pinfunction "2_2") (pintype "passive"))
      (node (ref "L8") (pin "1") (pinfunction "1_1") (pintype "passive"))
    )
    (net (code "70") (name "Net-(C33-Pad2)") (class "Default")
      (node (ref "C33") (pin "2") (pinfunction "2_2") (pintype "passive"))
      (node (ref "R12") (pin "2") (pinfunction "2_2") (pintype "passive"))
      (node (ref "R13") (pin "2") (pinfunction "2_2") (pintype "passive"))
    )
    (net (code "71") (name "Net-(IC1A-I0)") (class "Default")
      (node (ref "IC1") (pin "1") (pinfunction "I0_1") (pintype "input"))
      (node (ref "IC1") (pin "4") (pinfunction "I0_4") (pintype "input"))
      (node (ref "IC1") (pin "9") (pinfunction "I0_9") (pintype "input"))
      (node (ref "IC2") (pin "8") (pinfunction "O_8") (pintype "output"))
    )
    (net (code "72") (name "Net-(IC1A-I1)") (class "Default")
      (node (ref "IC1") (pin "2") (pinfunction "I1_2") (pintype "input"))
      (node (ref "IC24") (pin "1") (pinfunction "O_1") (pintype "output"))
    )
    (net (code "73") (name "Net-(IC1A-O)") (class "Default")
      (node (ref "IC1") (pin "3") (pinfunction "O_3") (pintype "output"))
      (node (ref "IC2") (pin "5") (pinfunction "I_5") (pintype "input"))
    )
    (net (code "74") (name "Net-(IC1B-I1)") (class "Default")
      (node (ref "IC1") (pin "5") (pinfunction "I1_5") (pintype "input"))
      (node (ref "IC24") (pin "4") (pinfunction "O_4") (pintype "output"))
    )
    (net (code "75") (name "Net-(IC1C-I1)") (class "Default")
      (node (ref "IC1") (pin "10") (pinfunction "I1_10") (pintype "input"))
      (node (ref "IC24") (pin "10") (pinfunction "O_10") (pintype "output"))
    )
    (net (code "76") (name "Net-(IC1D-I1)") (class "Default")
      (node (ref "IC1") (pin "13") (pinfunction "I1_13") (pintype "input"))
      (node (ref "IC2") (pin "10") (pinfunction "O_10") (pintype "output"))
      (node (ref "IC5") (pin "2") (pinfunction "I_2") (pintype "input"))
    )
    (net (code "77") (name "Net-(IC1D-O)") (class "Default")
      (node (ref "IC1") (pin "11") (pinfunction "O_11") (pintype "output"))
      (node (ref "IC2") (pin "9") (pinfunction "I_9") (pintype "input"))
    )
    (net (code "78") (name "Net-(IC2F-O)") (class "Default")
      (node (ref "D2") (pin "A") (pinfunction "A_A") (pintype "passive"))
      (node (ref "IC2") (pin "12") (pinfunction "O_12") (pintype "output"))
      (node (ref "R16") (pin "1") (pinfunction "1_1") (pintype "passive"))
    )
    (net (code "79") (name "Net-(IC5A-O)") (class "Default")
      (node (ref "IC5") (pin "4") (pinfunction "O_4") (pintype "output"))
      (node (ref "R17") (pin "2") (pinfunction "2_2") (pintype "passive"))
    )
    (net (code "80") (name "Net-(IC7A-O)") (class "Default")
      (node (ref "IC7") (pin "4") (pinfunction "O_4") (pintype "output"))
      (node (ref "U$7") (pin "12") (pinfunction "CLR_12") (pintype "input"))
      (node (ref "U$7") (pin "2") (pinfunction "CLR_2") (pintype "input"))
      (node (ref "U$8") (pin "12") (pinfunction "CLR_12") (pintype "input"))
      (node (ref "U$8") (pin "2") (pinfunction "CLR_2") (pintype "input"))
    )
    (net (code "81") (name "Net-(IC8A-1B1)") (class "Default")
      (node (ref "IC8") (pin "2") (pinfunction "1B1_2") (pintype "bidirectional"))
      (node (ref "U$2") (pin "7") (pinfunction "D0_7") (pintype "tri_state"))
      (node (ref "U$3") (pin "14") (pinfunction "D$1_14") (pintype "bidirectional"))
    )
    (net (code "82") (name "Net-(IC8A-1B2)") (class "Default")
      (node (ref "IC8") (pin "3") (pinfunction "1B2_3") (pintype "bidirectional"))
      (node (ref "U$2") (pin "8") (pinfunction "D1_8") (pintype "tri_state"))
      (node (ref "U$3") (pin "13") (pinfunction "D$2_13") (pintype "bidirectional"))
    )
    (net (code "83") (name "Net-(IC8A-1B3)") (class "Default")
      (node (ref "IC8") (pin "5") (pinfunction "1B3_5") (pintype "bidirectional"))
      (node (ref "U$2") (pin "9") (pinfunction "D2_9") (pintype "tri_state"))
      (node (ref "U$3") (pin "12") (pinfunction "D$3_12") (pintype "bidirectional"))
    )
    (net (code "84") (name "Net-(IC8A-1B4)") (class "Default")
      (node (ref "IC8") (pin "6") (pinfunction "1B4_6") (pintype "bidirectional"))
      (node (ref "U$2") (pin "10") (pinfunction "D3_10") (pintype "tri_state"))
      (node (ref "U$3") (pin "11") (pinfunction "D$4_11") (pintype "bidirectional"))
    )
    (net (code "85") (name "Net-(IC8A-1B5)") (class "Default")
      (node (ref "IC8") (pin "8") (pinfunction "1B5_8") (pintype "bidirectional"))
      (node (ref "U$2") (pin "13") (pinfunction "D4_13") (pintype "tri_state"))
      (node (ref "U$3") (pin "10") (pinfunction "D$5_10") (pintype "bidirectional"))
    )
    (net (code "86") (name "Net-(IC8A-1B6)") (class "Default")
      (node (ref "IC8") (pin "9") (pinfunction "1B6_9") (pintype "bidirectional"))
      (node (ref "U$2") (pin "14") (pinfunction "D5_14") (pintype "tri_state"))
      (node (ref "U$3") (pin "9") (pinfunction "D$6_9") (pintype "bidirectional"))
    )
    (net (code "87") (name "Net-(IC8A-1B7)") (class "Default")
      (node (ref "IC8") (pin "11") (pinfunction "1B7_11") (pintype "bidirectional"))
      (node (ref "U$2") (pin "15") (pinfunction "D6_15") (pintype "tri_state"))
      (node (ref "U$3") (pin "8") (pinfunction "D$7_8") (pintype "bidirectional"))
    )
    (net (code "88") (name "Net-(IC8A-1B8)") (class "Default")
      (node (ref "IC8") (pin "12") (pinfunction "1B8_12") (pintype "bidirectional"))
      (node (ref "U$2") (pin "16") (pinfunction "D7_16") (pintype "tri_state"))
      (node (ref "U$3") (pin "7") (pinfunction "D$8_7") (pintype "bidirectional"))
    )
    (net (code "89") (name "Net-(IC8A-2B1)") (class "Default")
      (node (ref "IC8") (pin "13") (pinfunction "2B1_13") (pintype "bidirectional"))
      (node (ref "U$2") (pin "29") (pinfunction "D8_29") (pintype "tri_state"))
      (node (ref "U$3") (pin "6") (pinfunction "D$9_6") (pintype "bidirectional"))
    )
    (net (code "90") (name "Net-(IC8A-2B2)") (class "Default")
      (node (ref "IC8") (pin "14") (pinfunction "2B2_14") (pintype "bidirectional"))
      (node (ref "U$2") (pin "30") (pinfunction "D9_30") (pintype "tri_state"))
      (node (ref "U$3") (pin "5") (pinfunction "D$10_5") (pintype "bidirectional"))
    )
    (net (code "91") (name "Net-(IC8A-2B3)") (class "Default")
      (node (ref "IC8") (pin "16") (pinfunction "2B3_16") (pintype "bidirectional"))
      (node (ref "U$2") (pin "31") (pinfunction "D10_31") (pintype "tri_state"))
      (node (ref "U$3") (pin "4") (pinfunction "D$11_4") (pintype "bidirectional"))
    )
    (net (code "92") (name "Net-(IC8A-2B4)") (class "Default")
      (node (ref "IC8") (pin "17") (pinfunction "2B4_17") (pintype "bidirectional"))
      (node (ref "U$2") (pin "32") (pinfunction "D11_32") (pintype "tri_state"))
      (node (ref "U$3") (pin "3") (pinfunction "D$12_3") (pintype "bidirectional"))
    )
    (net (code "93") (name "Net-(IC8A-2B5)") (class "Default")
      (node (ref "IC8") (pin "19") (pinfunction "2B5_19") (pintype "bidirectional"))
      (node (ref "U$2") (pin "35") (pinfunction "D12_35") (pintype "tri_state"))
      (node (ref "U$3") (pin "2") (pinfunction "D$13_2") (pintype "bidirectional"))
    )
    (net (code "94") (name "Net-(IC8A-2B6)") (class "Default")
      (node (ref "IC8") (pin "20") (pinfunction "2B6_20") (pintype "bidirectional"))
      (node (ref "U$2") (pin "36") (pinfunction "D13_36") (pintype "tri_state"))
      (node (ref "U$3") (pin "1") (pinfunction "D$14_1") (pintype "bidirectional"))
    )
    (net (code "95") (name "Net-(IC8A-2B8)") (class "Default")
      (node (ref "IC8") (pin "23") (pinfunction "2B8_23") (pintype "bidirectional"))
      (node (ref "U$2") (pin "38") (pinfunction "D15_38") (pintype "tri_state"))
    )
    (net (code "96") (name "Net-(IC9A-1B1)") (class "Default")
      (node (ref "IC9") (pin "2") (pinfunction "1B1_2") (pintype "bidirectional"))
      (node (ref "U$1") (pin "7") (pinfunction "D0_7") (pintype "tri_state"))
      (node (ref "U$4") (pin "14") (pinfunction "D$1_14") (pintype "bidirectional"))
    )
    (net (code "97") (name "Net-(IC9A-1B2)") (class "Default")
      (node (ref "IC9") (pin "3") (pinfunction "1B2_3") (pintype "bidirectional"))
      (node (ref "U$1") (pin "8") (pinfunction "D1_8") (pintype "tri_state"))
      (node (ref "U$4") (pin "13") (pinfunction "D$2_13") (pintype "bidirectional"))
    )
    (net (code "98") (name "Net-(IC9A-1B3)") (class "Default")
      (node (ref "IC9") (pin "5") (pinfunction "1B3_5") (pintype "bidirectional"))
      (node (ref "U$1") (pin "9") (pinfunction "D2_9") (pintype "tri_state"))
      (node (ref "U$4") (pin "12") (pinfunction "D$3_12") (pintype "bidirectional"))
    )
    (net (code "99") (name "Net-(IC9A-1B4)") (class "Default")
      (node (ref "IC9") (pin "6") (pinfunction "1B4_6") (pintype "bidirectional"))
      (node (ref "U$1") (pin "10") (pinfunction "D3_10") (pintype "tri_state"))
      (node (ref "U$4") (pin "11") (pinfunction "D$4_11") (pintype "bidirectional"))
    )
    (net (code "100") (name "Net-(IC9A-1B5)") (class "Default")
      (node (ref "IC9") (pin "8") (pinfunction "1B5_8") (pintype "bidirectional"))
      (node (ref "U$1") (pin "13") (pinfunction "D4_13") (pintype "tri_state"))
      (node (ref "U$4") (pin "10") (pinfunction "D$5_10") (pintype "bidirectional"))
    )
    (net (code "101") (name "Net-(IC9A-1B6)") (class "Default")
      (node (ref "IC9") (pin "9") (pinfunction "1B6_9") (pintype "bidirectional"))
      (node (ref "U$1") (pin "14") (pinfunction "D5_14") (pintype "tri_state"))
      (node (ref "U$4") (pin "9") (pinfunction "D$6_9") (pintype "bidirectional"))
    )
    (net (code "102") (name "Net-(IC9A-1B7)") (class "Default")
      (node (ref "IC9") (pin "11") (pinfunction "1B7_11") (pintype "bidirectional"))
      (node (ref "U$1") (pin "15") (pinfunction "D6_15") (pintype "tri_state"))
      (node (ref "U$4") (pin "8") (pinfunction "D$7_8") (pintype "bidirectional"))
    )
    (net (code "103") (name "Net-(IC9A-1B8)") (class "Default")
      (node (ref "IC9") (pin "12") (pinfunction "1B8_12") (pintype "bidirectional"))
      (node (ref "U$1") (pin "16") (pinfunction "D7_16") (pintype "tri_state"))
      (node (ref "U$4") (pin "7") (pinfunction "D$8_7") (pintype "bidirectional"))
    )
    (net (code "104") (name "Net-(IC9A-2B1)") (class "Default")
      (node (ref "IC9") (pin "13") (pinfunction "2B1_13") (pintype "bidirectional"))
      (node (ref "U$1") (pin "29") (pinfunction "D8_29") (pintype "tri_state"))
      (node (ref "U$4") (pin "6") (pinfunction "D$9_6") (pintype "bidirectional"))
    )
    (net (code "105") (name "Net-(IC9A-2B2)") (class "Default")
      (node (ref "IC9") (pin "14") (pinfunction "2B2_14") (pintype "bidirectional"))
      (node (ref "U$1") (pin "30") (pinfunction "D9_30") (pintype "tri_state"))
      (node (ref "U$4") (pin "5") (pinfunction "D$10_5") (pintype "bidirectional"))
    )
    (net (code "106") (name "Net-(IC9A-2B3)") (class "Default")
      (node (ref "IC9") (pin "16") (pinfunction "2B3_16") (pintype "bidirectional"))
      (node (ref "U$1") (pin "31") (pinfunction "D10_31") (pintype "tri_state"))
      (node (ref "U$4") (pin "4") (pinfunction "D$11_4") (pintype "bidirectional"))
    )
    (net (code "107") (name "Net-(IC9A-2B4)") (class "Default")
      (node (ref "IC9") (pin "17") (pinfunction "2B4_17") (pintype "bidirectional"))
      (node (ref "U$1") (pin "32") (pinfunction "D11_32") (pintype "tri_state"))
      (node (ref "U$4") (pin "3") (pinfunction "D$12_3") (pintype "bidirectional"))
    )
    (net (code "108") (name "Net-(IC9A-2B5)") (class "Default")
      (node (ref "IC9") (pin "19") (pinfunction "2B5_19") (pintype "bidirectional"))
      (node (ref "U$1") (pin "35") (pinfunction "D12_35") (pintype "tri_state"))
      (node (ref "U$4") (pin "2") (pinfunction "D$13_2") (pintype "bidirectional"))
    )
    (net (code "109") (name "Net-(IC9A-2B6)") (class "Default")
      (node (ref "IC9") (pin "20") (pinfunction "2B6_20") (pintype "bidirectional"))
      (node (ref "U$1") (pin "36") (pinfunction "D13_36") (pintype "tri_state"))
      (node (ref "U$4") (pin "1") (pinfunction "D$14_1") (pintype "bidirectional"))
    )
    (net (code "110") (name "Net-(IC9A-2B7)") (class "Default")
      (node (ref "IC9") (pin "22") (pinfunction "2B7_22") (pintype "bidirectional"))
      (node (ref "U$1") (pin "37") (pinfunction "D14_37") (pintype "tri_state"))
    )
    (net (code "111") (name "Net-(IC9A-2B8)") (class "Default")
      (node (ref "IC9") (pin "23") (pinfunction "2B8_23") (pintype "bidirectional"))
      (node (ref "U$1") (pin "38") (pinfunction "D15_38") (pintype "tri_state"))
    )
    (net (code "112") (name "Net-(IC10A-1A1)") (class "Default")
      (node (ref "IC10") (pin "47") (pinfunction "1A1_47") (pintype "input"))
      (node (ref "J1") (pin "C1") (pinfunction "C1_C1") (pintype "passive"))
    )
    (net (code "113") (name "Net-(IC10A-1A2)") (class "Default")
      (node (ref "IC10") (pin "46") (pinfunction "1A2_46") (pintype "input"))
      (node (ref "J1") (pin "C2") (pinfunction "C2_C2") (pintype "passive"))
    )
    (net (code "114") (name "Net-(IC10A-1A3)") (class "Default")
      (node (ref "IC10") (pin "44") (pinfunction "1A3_44") (pintype "input"))
      (node (ref "J1") (pin "C3") (pinfunction "C3_C3") (pintype "passive"))
    )
    (net (code "115") (name "Net-(IC10A-1A4)") (class "Default")
      (node (ref "IC10") (pin "43") (pinfunction "1A4_43") (pintype "input"))
      (node (ref "J1") (pin "C4") (pinfunction "C4_C4") (pintype "passive"))
    )
    (net (code "116") (name "Net-(IC10A-2A1)") (class "Default")
      (node (ref "IC10") (pin "41") (pinfunction "2A1_41") (pintype "input"))
      (node (ref "J1") (pin "C5") (pinfunction "C5_C5") (pintype "passive"))
    )
    (net (code "117") (name "Net-(IC10A-2A2)") (class "Default")
      (node (ref "IC10") (pin "40") (pinfunction "2A2_40") (pintype "input"))
      (node (ref "J1") (pin "C6") (pinfunction "C6_C6") (pintype "passive"))
    )
    (net (code "118") (name "Net-(IC10A-2A3)") (class "Default")
      (node (ref "IC10") (pin "38") (pinfunction "2A3_38") (pintype "input"))
      (node (ref "J1") (pin "C7") (pinfunction "C7_C7") (pintype "passive"))
    )
    (net (code "119") (name "Net-(IC10A-2A4)") (class "Default")
      (node (ref "IC10") (pin "37") (pinfunction "2A4_37") (pintype "input"))
      (node (ref "J1") (pin "C8") (pinfunction "C8_C8") (pintype "passive"))
    )
    (net (code "120") (name "Net-(IC10A-3A1)") (class "Default")
      (node (ref "IC10") (pin "36") (pinfunction "3A1_36") (pintype "input"))
      (node (ref "J1") (pin "C9") (pinfunction "C9_C9") (pintype "passive"))
    )
    (net (code "121") (name "Net-(IC10A-3A2)") (class "Default")
      (node (ref "IC10") (pin "35") (pinfunction "3A2_35") (pintype "input"))
      (node (ref "J1") (pin "C10") (pinfunction "C10_C10") (pintype "passive"))
    )
    (net (code "122") (name "Net-(IC10A-3A3)") (class "Default")
      (node (ref "IC10") (pin "33") (pinfunction "3A3_33") (pintype "input"))
      (node (ref "J1") (pin "C11") (pinfunction "C11_C11") (pintype "passive"))
    )
    (net (code "123") (name "Net-(IC10A-3A4)") (class "Default")
      (node (ref "IC10") (pin "32") (pinfunction "3A4_32") (pintype "input"))
      (node (ref "J1") (pin "C12") (pinfunction "C12_C12") (pintype "passive"))
    )
    (net (code "124") (name "Net-(IC10A-4A1)") (class "Default")
      (node (ref "IC10") (pin "30") (pinfunction "4A1_30") (pintype "input"))
      (node (ref "J1") (pin "C13") (pinfunction "C13_C13") (pintype "passive"))
    )
    (net (code "125") (name "Net-(IC10A-4A2)") (class "Default")
      (node (ref "IC10") (pin "29") (pinfunction "4A2_29") (pintype "input"))
      (node (ref "J1") (pin "C14") (pinfunction "C14_C14") (pintype "passive"))
    )
    (net (code "126") (name "Net-(IC10A-4A3)") (class "Default")
      (node (ref "IC10") (pin "27") (pinfunction "4A3_27") (pintype "input"))
      (node (ref "J1") (pin "C15") (pinfunction "C15_C15") (pintype "passive"))
    )
    (net (code "127") (name "Net-(IC10A-4A4)") (class "Default")
      (node (ref "IC10") (pin "26") (pinfunction "4A4_26") (pintype "input"))
      (node (ref "J1") (pin "C16") (pinfunction "C16_C16") (pintype "passive"))
    )
    (net (code "128") (name "Net-(IC11A-O)") (class "Default")
      (node (ref "IC11") (pin "4") (pinfunction "O_4") (pintype "output"))
      (node (ref "U$5") (pin "1") (pinfunction "CLK_IN_1") (pintype "bidirectional"))
    )
    (net (code "129") (name "Net-(IC13A-I)") (class "Default")
      (node (ref "C17") (pin "1") (pinfunction "1_1") (pintype "passive"))
      (node (ref "D1") (pin "C") (pinfunction "C_C") (pintype "passive"))
      (node (ref "IC13") (pin "2") (pinfunction "I_2") (pintype "input"))
      (node (ref "R15") (pin "2") (pinfunction "2_2") (pintype "passive"))
    )
    (net (code "130") (name "Net-(IC14A-I)") (class "Default")
      (node (ref "C18") (pin "1") (pinfunction "1_1") (pintype "passive"))
      (node (ref "D2") (pin "C") (pinfunction "C_C") (pintype "passive"))
      (node (ref "IC14") (pin "2") (pinfunction "I_2") (pintype "input"))
      (node (ref "R16") (pin "2") (pinfunction "2_2") (pintype "passive"))
    )
    (net (code "131") (name "Net-(IC15A-I0)") (class "Default")
      (node (ref "IC15") (pin "1") (pinfunction "I0_1") (pintype "input"))
      (node (ref "IC8") (pin "22") (pinfunction "2B7_22") (pintype "bidirectional"))
      (node (ref "U$2") (pin "37") (pinfunction "D14_37") (pintype "tri_state"))
    )
    (net (code "132") (name "Net-(IC15A-O)") (class "Default")
      (node (ref "IC15") (pin "4") (pinfunction "O_4") (pintype "output"))
      (node (ref "X3") (pin "1") (pinfunction "1_1") (pintype "passive"))
    )
    (net (code "133") (name "Net-(IC16A-P=Q)") (class "Default")
      (node (ref "IC16") (pin "19") (pinfunction "P=Q_19") (pintype "output"))
      (node (ref "IC2") (pin "11") (pinfunction "I_11") (pintype "input"))
    )
    (net (code "134") (name "Net-(IC16A-Q0)") (class "Default")
      (node (ref "IC16") (pin "3") (pinfunction "Q0_3") (pintype "input"))
      (node (ref "R19") (pin "2") (pinfunction "2_2") (pintype "passive"))
      (node (ref "S1") (pin "16") (pinfunction "16_16") (pintype "passive"))
    )
    (net (code "135") (name "Net-(IC16A-Q1)") (class "Default")
      (node (ref "IC16") (pin "5") (pinfunction "Q1_5") (pintype "input"))
      (node (ref "R20") (pin "2") (pinfunction "2_2") (pintype "passive"))
      (node (ref "S1") (pin "15") (pinfunction "15_15") (pintype "passive"))
    )
    (net (code "136") (name "Net-(IC16A-Q2)") (class "Default")
      (node (ref "IC16") (pin "7") (pinfunction "Q2_7") (pintype "input"))
      (node (ref "R21") (pin "2") (pinfunction "2_2") (pintype "passive"))
      (node (ref "S1") (pin "14") (pinfunction "14_14") (pintype "passive"))
    )
    (net (code "137") (name "Net-(IC16A-Q3)") (class "Default")
      (node (ref "IC16") (pin "9") (pinfunction "Q3_9") (pintype "input"))
      (node (ref "R22") (pin "2") (pinfunction "2_2") (pintype "passive"))
      (node (ref "S1") (pin "13") (pinfunction "13_13") (pintype "passive"))
    )
    (net (code "138") (name "Net-(IC16A-Q4)") (class "Default")
      (node (ref "IC16") (pin "12") (pinfunction "Q4_12") (pintype "input"))
      (node (ref "R23") (pin "2") (pinfunction "2_2") (pintype "passive"))
      (node (ref "S1") (pin "12") (pinfunction "12_12") (pintype "passive"))
    )
    (net (code "139") (name "Net-(IC16A-Q5)") (class "Default")
      (node (ref "IC16") (pin "14") (pinfunction "Q5_14") (pintype "input"))
      (node (ref "R24") (pin "2") (pinfunction "2_2") (pintype "passive"))
      (node (ref "S1") (pin "11") (pinfunction "11_11") (pintype "passive"))
    )
    (net (code "140") (name "Net-(IC16A-Q6)") (class "Default")
      (node (ref "IC16") (pin "16") (pinfunction "Q6_16") (pintype "input"))
      (node (ref "R25") (pin "2") (pinfunction "2_2") (pintype "passive"))
      (node (ref "S1") (pin "10") (pinfunction "10_10") (pintype "passive"))
    )
    (net (code "141") (name "Net-(IC16A-Q7)") (class "Default")
      (node (ref "IC16") (pin "18") (pinfunction "Q7_18") (pintype "input"))
      (node (ref "R26") (pin "2") (pinfunction "2_2") (pintype "passive"))
      (node (ref "S1") (pin "9") (pinfunction "9_9") (pintype "passive"))
    )
    (net (code "142") (name "Net-(IC18A-O)") (class "Default")
      (node (ref "D1") (pin "A") (pinfunction "A_A") (pintype "passive"))
      (node (ref "IC18") (pin "4") (pinfunction "O_4") (pintype "output"))
      (node (ref "IC2") (pin "13") (pinfunction "I_13") (pintype "input"))
      (node (ref "R15") (pin "1") (pinfunction "1_1") (pintype "passive"))
    )
    (net (code "143") (name "Net-(IC20A-1A1)") (class "Default")
      (node (ref "IC20") (pin "47") (pinfunction "1A1_47") (pintype "input"))
      (node (ref "J1") (pin "C17") (pinfunction "C17_C17") (pintype "passive"))
    )
    (net (code "144") (name "Net-(IC20A-1A2)") (class "Default")
      (node (ref "IC20") (pin "46") (pinfunction "1A2_46") (pintype "input"))
      (node (ref "J1") (pin "C18") (pinfunction "C18_C18") (pintype "passive"))
    )
    (net (code "145") (name "Net-(IC20A-1A3)") (class "Default")
      (node (ref "IC20") (pin "44") (pinfunction "1A3_44") (pintype "input"))
      (node (ref "J1") (pin "C19") (pinfunction "C19_C19") (pintype "passive"))
    )
    (net (code "146") (name "Net-(IC20A-1A4)") (class "Default")
      (node (ref "IC20") (pin "43") (pinfunction "1A4_43") (pintype "input"))
      (node (ref "J1") (pin "C20") (pinfunction "C20_C20") (pintype "passive"))
    )
    (net (code "147") (name "Net-(IC20A-2A1)") (class "Default")
      (node (ref "IC20") (pin "41") (pinfunction "2A1_41") (pintype "input"))
      (node (ref "J1") (pin "C21") (pinfunction "C21_C21") (pintype "passive"))
    )
    (net (code "148") (name "Net-(IC20A-2A2)") (class "Default")
      (node (ref "IC20") (pin "40") (pinfunction "2A2_40") (pintype "input"))
      (node (ref "J1") (pin "C22") (pinfunction "C22_C22") (pintype "passive"))
    )
    (net (code "149") (name "Net-(IC20A-2A3)") (class "Default")
      (node (ref "IC20") (pin "38") (pinfunction "2A3_38") (pintype "input"))
      (node (ref "J1") (pin "C23") (pinfunction "C23_C23") (pintype "passive"))
    )
    (net (code "150") (name "Net-(IC20A-2A4)") (class "Default")
      (node (ref "IC20") (pin "37") (pinfunction "2A4_37") (pintype "input"))
      (node (ref "J1") (pin "C24") (pinfunction "C24_C24") (pintype "passive"))
    )
    (net (code "151") (name "Net-(IC20A-3A1)") (class "Default")
      (node (ref "IC20") (pin "36") (pinfunction "3A1_36") (pintype "input"))
      (node (ref "J1") (pin "C25") (pinfunction "C25_C25") (pintype "passive"))
    )
    (net (code "152") (name "Net-(IC20A-3A2)") (class "Default")
      (node (ref "IC20") (pin "35") (pinfunction "3A2_35") (pintype "input"))
      (node (ref "J1") (pin "C26") (pinfunction "C26_C26") (pintype "passive"))
    )
    (net (code "153") (name "Net-(IC20A-3A3)") (class "Default")
      (node (ref "IC20") (pin "33") (pinfunction "3A3_33") (pintype "input"))
      (node (ref "J1") (pin "C27") (pinfunction "C27_C27") (pintype "passive"))
    )
    (net (code "154") (name "Net-(IC20A-3A4)") (class "Default")
      (node (ref "IC20") (pin "32") (pinfunction "3A4_32") (pintype "input"))
      (node (ref "J1") (pin "C28") (pinfunction "C28_C28") (pintype "passive"))
    )
    (net (code "155") (name "Net-(IC20A-4A1)") (class "Default")
      (node (ref "IC20") (pin "30") (pinfunction "4A1_30") (pintype "input"))
      (node (ref "J1") (pin "C29") (pinfunction "C29_C29") (pintype "passive"))
    )
    (net (code "156") (name "Net-(IC20A-4A2)") (class "Default")
      (node (ref "IC20") (pin "29") (pinfunction "4A2_29") (pintype "input"))
      (node (ref "J1") (pin "C30") (pinfunction "C30_C30") (pintype "passive"))
    )
    (net (code "157") (name "Net-(IC20A-4A3)") (class "Default")
      (node (ref "IC20") (pin "27") (pinfunction "4A3_27") (pintype "input"))
      (node (ref "J1") (pin "C31") (pinfunction "C31_C31") (pintype "passive"))
    )
    (net (code "158") (name "Net-(IC20A-4A4)") (class "Default")
      (node (ref "IC20") (pin "26") (pinfunction "4A4_26") (pintype "input"))
      (node (ref "J1") (pin "C32") (pinfunction "C32_C32") (pintype "passive"))
    )
    (net (code "159") (name "Net-(IC24B-I0)") (class "Default")
      (node (ref "IC2") (pin "2") (pinfunction "O_2") (pintype "output"))
      (node (ref "IC24") (pin "5") (pinfunction "I0_5") (pintype "input"))
    )
    (net (code "160") (name "Net-(IC24C-I1)") (class "Default")
      (node (ref "IC2") (pin "4") (pinfunction "O_4") (pintype "output"))
      (node (ref "IC24") (pin "9") (pinfunction "I1_9") (pintype "input"))
    )
    (net (code "161") (name "Net-(IC24D-I0)") (class "Default")
      (node (ref "IC24") (pin "11") (pinfunction "I0_11") (pintype "input"))
      (node (ref "IC3") (pin "19") (pinfunction "P=Q_19") (pintype "output"))
    )
    (net (code "162") (name "Net-(IC24D-I1)") (class "Default")
      (node (ref "IC24") (pin "12") (pinfunction "I1_12") (pintype "input"))
      (node (ref "IC4") (pin "19") (pinfunction "P=Q_19") (pintype "output"))
    )
    (net (code "163") (name "Net-(LED1-PadA)") (class "Default")
      (node (ref "LED1") (pin "A") (pinfunction "A_A") (pintype "passive"))
      (node (ref "R17") (pin "1") (pinfunction "1_1") (pintype "passive"))
    )
    (net (code "164") (name "Net-(R13-Pad1)") (class "Default")
      (node (ref "R13") (pin "1") (pinfunction "1_1") (pintype "passive"))
      (node (ref "R14") (pin "1") (pinfunction "1_1") (pintype "passive"))
      (node (ref "X2") (pin "1") (pinfunction "1_1") (pintype "passive"))
    )
    (net (code "165") (name "Net-(U$3-FSADJ)") (class "Default")
      (node (ref "R4") (pin "1") (pinfunction "1_1") (pintype "passive"))
      (node (ref "U$3") (pin "18") (pinfunction "FSADJ_18") (pintype "bidirectional"))
    )
    (net (code "166") (name "Net-(U$3-ICOMP)") (class "Default")
      (node (ref "C12") (pin "1") (pinfunction "1_1") (pintype "passive"))
      (node (ref "U$3") (pin "23") (pinfunction "ICOMP_23") (pintype "bidirectional"))
    )
    (net (code "167") (name "Net-(U$3-IOUTA)") (class "Default")
      (node (ref "C5") (pin "1") (pinfunction "1_1") (pintype "passive"))
      (node (ref "L1") (pin "1") (pinfunction "1_1") (pintype "passive"))
      (node (ref "R6") (pin "1") (pinfunction "1_1") (pintype "passive"))
      (node (ref "U$3") (pin "22") (pinfunction "IOUTA_22") (pintype "bidirectional"))
    )
    (net (code "168") (name "Net-(U$3-IOUTB)") (class "Default")
      (node (ref "C5") (pin "2") (pinfunction "2_2") (pintype "passive"))
      (node (ref "L2") (pin "1") (pinfunction "1_1") (pintype "passive"))
      (node (ref "R7") (pin "2") (pinfunction "2_2") (pintype "passive"))
      (node (ref "U$3") (pin "21") (pinfunction "IOUTB_21") (pintype "bidirectional"))
    )
    (net (code "169") (name "Net-(U$3-REFIO)") (class "Default")
      (node (ref "C3") (pin "2") (pinfunction "2_2") (pintype "passive"))
      (node (ref "U$3") (pin "17") (pinfunction "REFIO_17") (pintype "bidirectional"))
    )
    (net (code "170") (name "Net-(U$4-FSADJ)") (class "Default")
      (node (ref "R5") (pin "1") (pinfunction "1_1") (pintype "passive"))
      (node (ref "U$4") (pin "18") (pinfunction "FSADJ_18") (pintype "bidirectional"))
    )
    (net (code "171") (name "Net-(U$4-ICOMP)") (class "Default")
      (node (ref "C11") (pin "1") (pinfunction "1_1") (pintype "passive"))
      (node (ref "U$4") (pin "23") (pinfunction "ICOMP_23") (pintype "bidirectional"))
    )
    (net (code "172") (name "Net-(U$4-IOUTA)") (class "Default")
      (node (ref "C8") (pin "1") (pinfunction "1_1") (pintype "passive"))
      (node (ref "L5") (pin "1") (pinfunction "1_1") (pintype "passive"))
      (node (ref "R8") (pin "1") (pinfunction "1_1") (pintype "passive"))
      (node (ref "U$4") (pin "22") (pinfunction "IOUTA_22") (pintype "bidirectional"))
    )
    (net (code "173") (name "Net-(U$4-IOUTB)") (class "Default")
      (node (ref "C8") (pin "2") (pinfunction "2_2") (pintype "passive"))
      (node (ref "L6") (pin "1") (pinfunction "1_1") (pintype "passive"))
      (node (ref "R9") (pin "2") (pinfunction "2_2") (pintype "passive"))
      (node (ref "U$4") (pin "21") (pinfunction "IOUTB_21") (pintype "bidirectional"))
    )
    (net (code "174") (name "Net-(U$4-REFIO)") (class "Default")
      (node (ref "C4") (pin "2") (pinfunction "2_2") (pintype "passive"))
      (node (ref "U$4") (pin "17") (pinfunction "REFIO_17") (pintype "bidirectional"))
    )
    (net (code "175") (name "Net-(U$5-4NS)") (class "Default")
      (node (ref "JP1") (pin "1") (pinfunction "1_1") (pintype "passive"))
      (node (ref "U$5") (pin "7") (pinfunction "4NS_7") (pintype "bidirectional"))
    )
    (net (code "176") (name "Net-(U$5-8NS)") (class "Default")
      (node (ref "JP1") (pin "3") (pinfunction "3_3") (pintype "passive"))
      (node (ref "U$5") (pin "2") (pinfunction "8NS_2") (pintype "bidirectional"))
    )
    (net (code "177") (name "Net-(U$5-12NS)") (class "Default")
      (node (ref "JP1") (pin "5") (pinfunction "5_5") (pintype "passive"))
      (node (ref "U$5") (pin "6") (pinfunction "12NS_6") (pintype "bidirectional"))
    )
    (net (code "178") (name "Net-(U$5-16NS)") (class "Default")
      (node (ref "JP1") (pin "7") (pinfunction "7_7") (pintype "passive"))
      (node (ref "U$5") (pin "3") (pinfunction "16NS_3") (pintype "bidirectional"))
    )
    (net (code "179") (name "Net-(U$6-P$5)") (class "Default")
      (node (ref "C15") (pin "2") (pinfunction "2_2") (pintype "passive"))
      (node (ref "U$6") (pin "5") (pinfunction "P$5_5") (pintype "bidirectional"))
    )
    (net (code "180") (name "Net-(U$6-P$6)") (class "Default")
      (node (ref "C16") (pin "2") (pinfunction "2_2") (pintype "passive"))
      (node (ref "U$6") (pin "6") (pinfunction "P$6_6") (pintype "bidirectional"))
    )
    (net (code "181") (name "Net-(U$6-P$11)") (class "Default")
      (node (ref "C33") (pin "1") (pinfunction "1_1") (pintype "passive"))
      (node (ref "U$6") (pin "11") (pinfunction "P$11_11") (pintype "bidirectional"))
    )
    (net (code "182") (name "Net-(U$7A-A)") (class "Default")
      (node (ref "JP1") (pin "2") (pinfunction "2_2") (pintype "passive"))
      (node (ref "JP1") (pin "4") (pinfunction "4_4") (pintype "passive"))
      (node (ref "JP1") (pin "6") (pinfunction "6_6") (pintype "passive"))
      (node (ref "JP1") (pin "8") (pinfunction "8_8") (pintype "passive"))
      (node (ref "U$7") (pin "1") (pinfunction "A_1") (pintype "input"))
    )
    (net (code "183") (name "Net-(U$12-1)") (class "Default")
      (node (ref "C15") (pin "1") (pinfunction "1_1") (pintype "passive"))
      (node (ref "U$12") (pin "P$1") (pinfunction "1_P$1") (pintype "bidirectional"))
    )
    (net (code "184") (name "Net-(U$12-3)") (class "Default")
      (node (ref "C16") (pin "1") (pinfunction "1_1") (pintype "passive"))
      (node (ref "U$12") (pin "P$3") (pinfunction "3_P$3") (pintype "bidirectional"))
    )
    (net (code "185") (name "Net-(U$12-5)") (class "Default")
      (node (ref "R18") (pin "2") (pinfunction "2_2") (pintype "passive"))
      (node (ref "U$12") (pin "P$5") (pinfunction "5_P$5") (pintype "bidirectional"))
      (node (ref "X1") (pin "1") (pinfunction "1_1") (pintype "passive"))
    )
    (net (code "186") (name "OE_MEM") (class "Default")
      (node (ref "IC13") (pin "4") (pinfunction "O_4") (pintype "output"))
      (node (ref "U$1") (pin "41") (pinfunction "~{OE}_41") (pintype "input"))
      (node (ref "U$2") (pin "41") (pinfunction "~{OE}_41") (pintype "input"))
    )
    (net (code "187") (name "OE_SWITCH") (class "Default")
      (node (ref "IC14") (pin "4") (pinfunction "O_4") (pintype "output"))
      (node (ref "IC15") (pin "2") (pinfunction "I1_2") (pintype "input"))
      (node (ref "IC8") (pin "25") (pinfunction "2G_25") (pintype "input"))
      (node (ref "IC8") (pin "48") (pinfunction "1G_48") (pintype "input"))
      (node (ref "IC9") (pin "25") (pinfunction "2G_25") (pintype "input"))
      (node (ref "IC9") (pin "48") (pinfunction "1G_48") (pintype "input"))
      (node (ref "R2") (pin "2") (pinfunction "2_2") (pintype "passive"))
      (node (ref "R3") (pin "1") (pinfunction "1_1") (pintype "passive"))
    )
    (net (code "188") (name "PROG") (class "Default")
      (node (ref "IC18") (pin "2") (pinfunction "I_2") (pintype "input"))
      (node (ref "IC20") (pin "16") (pinfunction "3Y3_16") (pintype "tri_state"))
    )
    (net (code "189") (name "QBN") (class "Default")
      (node (ref "C7") (pin "1") (pinfunction "1_1") (pintype "passive"))
      (node (ref "L3") (pin "2") (pinfunction "2_2") (pintype "passive"))
      (node (ref "R10") (pin "2") (pinfunction "2_2") (pintype "passive"))
      (node (ref "U$6") (pin "15") (pinfunction "P$15_15") (pintype "bidirectional"))
    )
    (net (code "190") (name "QBP") (class "Default")
      (node (ref "C7") (pin "2") (pinfunction "2_2") (pintype "passive"))
      (node (ref "L4") (pin "2") (pinfunction "2_2") (pintype "passive"))
      (node (ref "R10") (pin "1") (pinfunction "1_1") (pintype "passive"))
      (node (ref "U$6") (pin "16") (pinfunction "P$16_16") (pintype "bidirectional"))
    )
    (net (code "191") (name "RES") (class "Default")
      (node (ref "IC20") (pin "17") (pinfunction "3Y4_17") (pintype "tri_state"))
      (node (ref "IC7") (pin "1") (pinfunction "I0_1") (pintype "input"))
      (node (ref "R1") (pin "1") (pinfunction "1_1") (pintype "passive"))
    )
    (net (code "192") (name "VCC") (class "Default")
      (node (ref "C14") (pin "1") (pinfunction "1_1") (pintype "passive"))
      (node (ref "C19") (pin "1") (pinfunction "1_1") (pintype "passive"))
      (node (ref "C20") (pin "1") (pinfunction "1_1") (pintype "passive"))
      (node (ref "C21") (pin "1") (pinfunction "1_1") (pintype "passive"))
      (node (ref "C22") (pin "1") (pinfunction "1_1") (pintype "passive"))
      (node (ref "C23") (pin "1") (pinfunction "1_1") (pintype "passive"))
      (node (ref "C24") (pin "1") (pinfunction "1_1") (pintype "passive"))
      (node (ref "C25") (pin "1") (pinfunction "1_1") (pintype "passive"))
      (node (ref "C26") (pin "1") (pinfunction "1_1") (pintype "passive"))
      (node (ref "C27") (pin "1") (pinfunction "1_1") (pintype "passive"))
      (node (ref "C28") (pin "1") (pinfunction "1_1") (pintype "passive"))
      (node (ref "C29") (pin "1") (pinfunction "1_1") (pintype "passive"))
      (node (ref "C30") (pin "1") (pinfunction "1_1") (pintype "passive"))
      (node (ref "C31") (pin "1") (pinfunction "1_1") (pintype "passive"))
      (node (ref "C34") (pin "1") (pinfunction "1_1") (pintype "passive"))
      (node (ref "C35") (pin "1") (pinfunction "1_1") (pintype "passive"))
      (node (ref "C36") (pin "1") (pinfunction "1_1") (pintype "passive"))
      (node (ref "C37") (pin "1") (pinfunction "1_1") (pintype "passive"))
      (node (ref "C38") (pin "1") (pinfunction "1_1") (pintype "passive"))
      (node (ref "C39") (pin "1") (pinfunction "1_1") (pintype "passive"))
      (node (ref "C40") (pin "1") (pinfunction "1_1") (pintype "passive"))
      (node (ref "IC8") (pin "1") (pinfunction "1DIR_1") (pintype "input"))
      (node (ref "IC8") (pin "24") (pinfunction "2DIR_24") (pintype "input"))
      (node (ref "IC9") (pin "1") (pinfunction "1DIR_1") (pintype "input"))
      (node (ref "IC9") (pin "24") (pinfunction "2DIR_24") (pintype "input"))
      (node (ref "R2") (pin "1") (pinfunction "1_1") (pintype "passive"))
      (node (ref "R3") (pin "2") (pinfunction "2_2") (pintype "passive"))
      (node (ref "S1") (pin "1") (pinfunction "1_1") (pintype "passive"))
      (node (ref "S1") (pin "2") (pinfunction "2_2") (pintype "passive"))
      (node (ref "S1") (pin "3") (pinfunction "3_3") (pintype "passive"))
      (node (ref "S1") (pin "4") (pinfunction "4_4") (pintype "passive"))
      (node (ref "S1") (pin "5") (pinfunction "5_5") (pintype "passive"))
      (node (ref "S1") (pin "6") (pinfunction "6_6") (pintype "passive"))
      (node (ref "S1") (pin "7") (pinfunction "7_7") (pintype "passive"))
      (node (ref "S1") (pin "8") (pinfunction "8_8") (pintype "passive"))
      (node (ref "U$1") (pin "11") (pinfunction "3.3V_11") (pintype "bidirectional"))
      (node (ref "U$1") (pin "33") (pinfunction "3.3V_33") (pintype "bidirectional"))
      (node (ref "U$2") (pin "11") (pinfunction "3.3V_11") (pintype "bidirectional"))
      (node (ref "U$2") (pin "33") (pinfunction "3.3V_33") (pintype "bidirectional"))
      (node (ref "U$3") (pin "27") (pinfunction "DVDD_27") (pintype "bidirectional"))
      (node (ref "U$4") (pin "27") (pinfunction "DVDD_27") (pintype "bidirectional"))
      (node (ref "U$5") (pin "8") (pinfunction "3.3V_8") (pintype "bidirectional"))
      (node (ref "U$9") (pin "2") (pinfunction "OUT_2") (pintype "bidirectional"))
      (node (ref "U$9") (pin "4") (pinfunction "OUT_4") (pintype "bidirectional"))
    )
    (net (code "193") (name "WE") (class "Default")
      (node (ref "IC1") (pin "12") (pinfunction "I0_12") (pintype "input"))
      (node (ref "IC20") (pin "20") (pinfunction "4Y2_20") (pintype "tri_state"))
    )
    (net (code "194") (name "WE_I") (class "Default")
      (node (ref "IC1") (pin "6") (pinfunction "O_6") (pintype "output"))
      (node (ref "U$2") (pin "17") (pinfunction "~{WE}_17") (pintype "input"))
    )
    (net (code "195") (name "WE_Q") (class "Default")
      (node (ref "IC1") (pin "8") (pinfunction "O_8") (pintype "output"))
      (node (ref "U$1") (pin "17") (pinfunction "~{WE}_17") (pintype "input"))
    )
    (net (code "196") (name "unconnected-(IC20A-4Y3-Pad22)") (class "Default")
      (node (ref "IC20") (pin "22") (pinfunction "4Y3_22") (pintype "tri_state"))
    )
    (net (code "197") (name "unconnected-(IC20A-4Y4-Pad23)") (class "Default")
      (node (ref "IC20") (pin "23") (pinfunction "4Y4_23") (pintype "tri_state"))
    )
    (net (code "198") (name "unconnected-(J1-PadA1)") (class "Default")
      (node (ref "J1") (pin "A1") (pinfunction "A1_A1") (pintype "passive"))
    )
    (net (code "199") (name "unconnected-(J1-PadA2)") (class "Default")
      (node (ref "J1") (pin "A2") (pinfunction "A2_A2") (pintype "passive"))
    )
    (net (code "200") (name "unconnected-(J1-PadA3)") (class "Default")
      (node (ref "J1") (pin "A3") (pinfunction "A3_A3") (pintype "passive"))
    )
    (net (code "201") (name "unconnected-(J1-PadA4)") (class "Default")
      (node (ref "J1") (pin "A4") (pinfunction "A4_A4") (pintype "passive"))
    )
    (net (code "202") (name "unconnected-(J1-PadA5)") (class "Default")
      (node (ref "J1") (pin "A5") (pinfunction "A5_A5") (pintype "passive"))
    )
    (net (code "203") (name "unconnected-(J1-PadA6)") (class "Default")
      (node (ref "J1") (pin "A6") (pinfunction "A6_A6") (pintype "passive"))
    )
    (net (code "204") (name "unconnected-(J1-PadA7)") (class "Default")
      (node (ref "J1") (pin "A7") (pinfunction "A7_A7") (pintype "passive"))
    )
    (net (code "205") (name "unconnected-(J1-PadA8)") (class "Default")
      (node (ref "J1") (pin "A8") (pinfunction "A8_A8") (pintype "passive"))
    )
    (net (code "206") (name "unconnected-(J1-PadA25)") (class "Default")
      (node (ref "J1") (pin "A25") (pinfunction "A25_A25") (pintype "passive"))
    )
    (net (code "207") (name "unconnected-(J1-PadA26)") (class "Default")
      (node (ref "J1") (pin "A26") (pinfunction "A26_A26") (pintype "passive"))
    )
    (net (code "208") (name "unconnected-(J1-PadA27)") (class "Default")
      (node (ref "J1") (pin "A27") (pinfunction "A27_A27") (pintype "passive"))
    )
    (net (code "209") (name "unconnected-(J1-PadA28)") (class "Default")
      (node (ref "J1") (pin "A28") (pinfunction "A28_A28") (pintype "passive"))
    )
    (net (code "210") (name "unconnected-(U$5-20NS-Pad5)") (class "Default")
      (node (ref "U$5") (pin "5") (pinfunction "20NS_5") (pintype "bidirectional"))
    )
  )
)
